# relaisarray.net
KiCad netlist of a schematic drawn in EAGLE
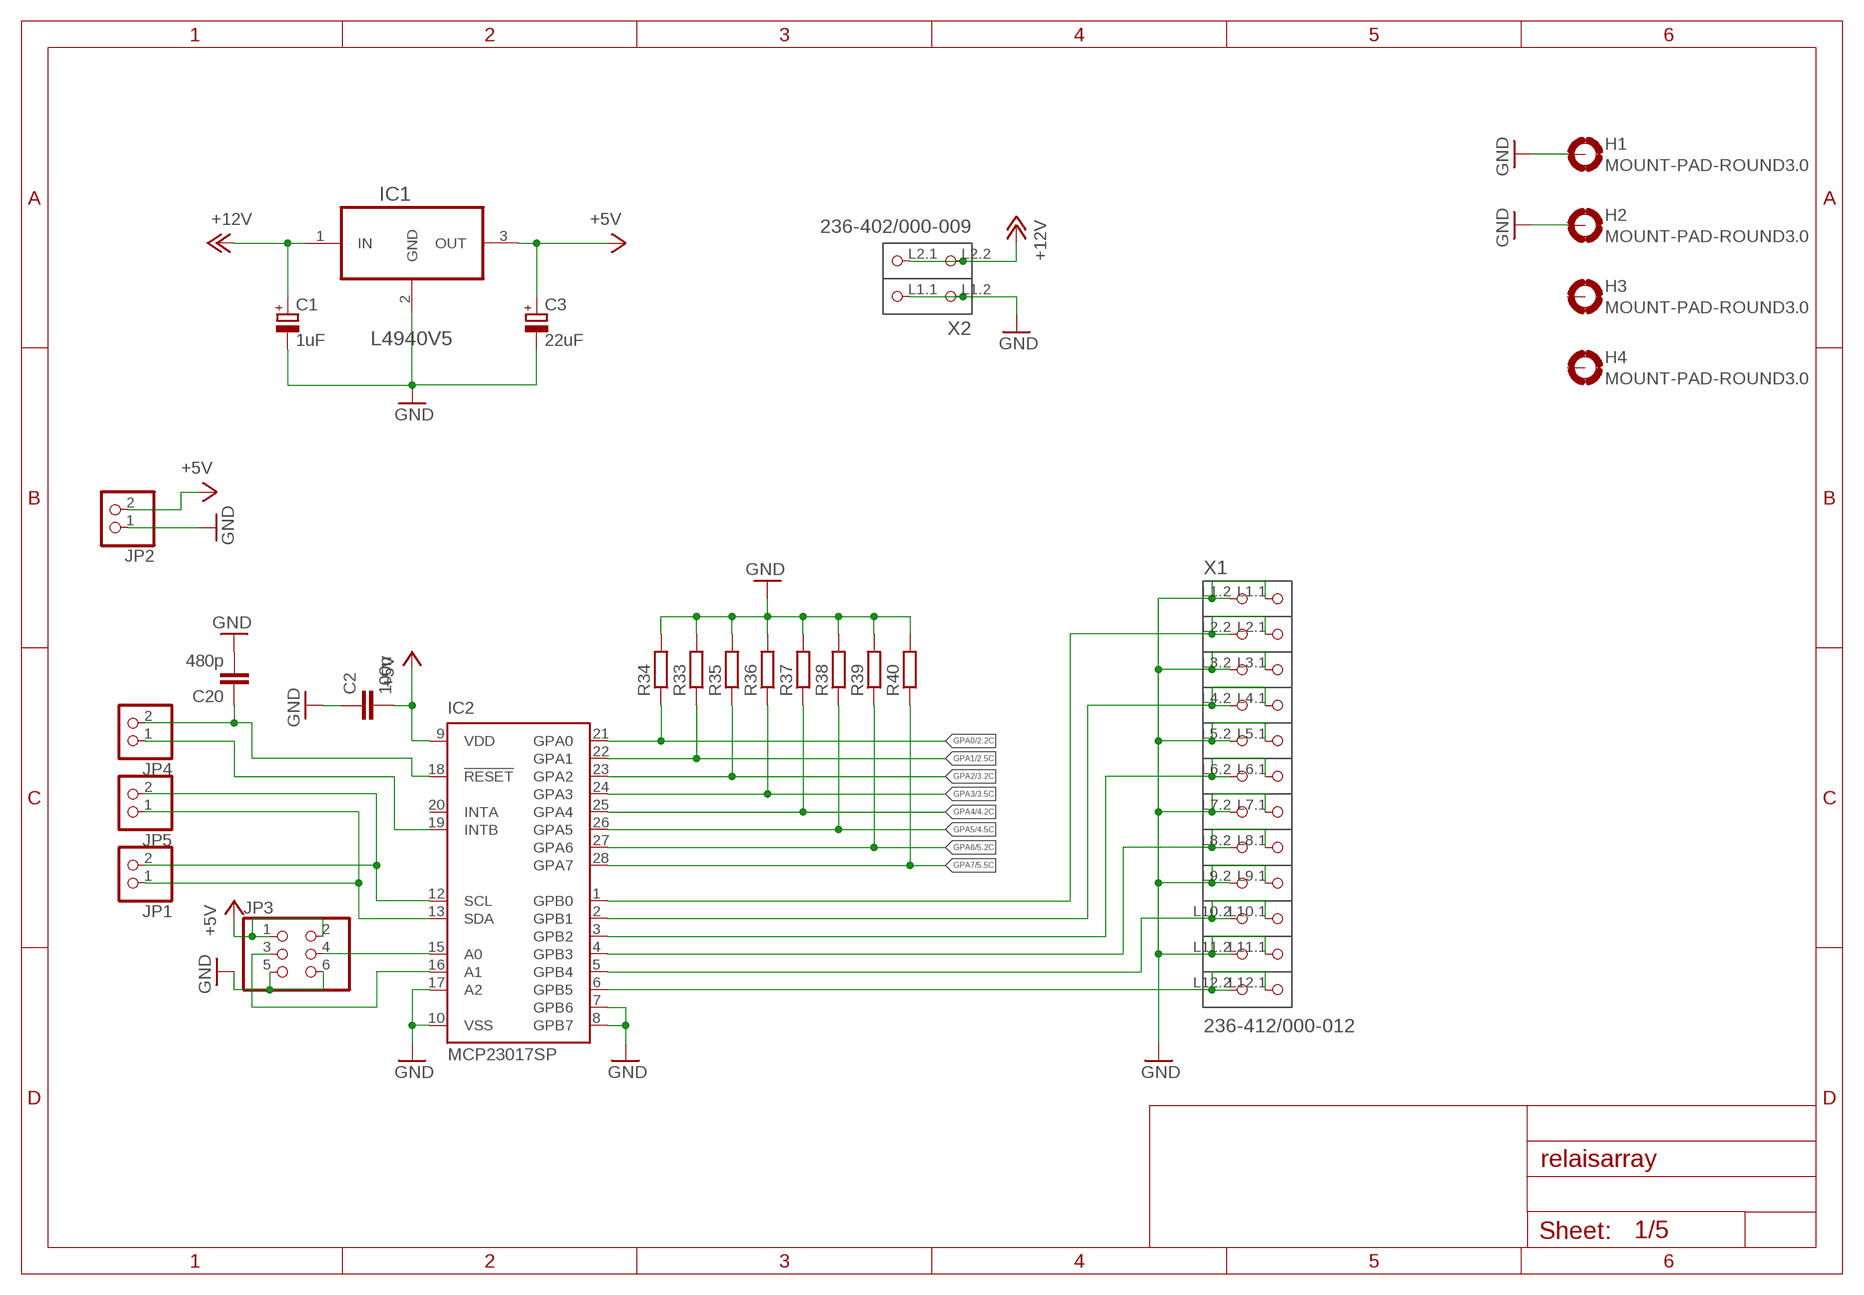
[diagram p0: schematic, sheet 1]
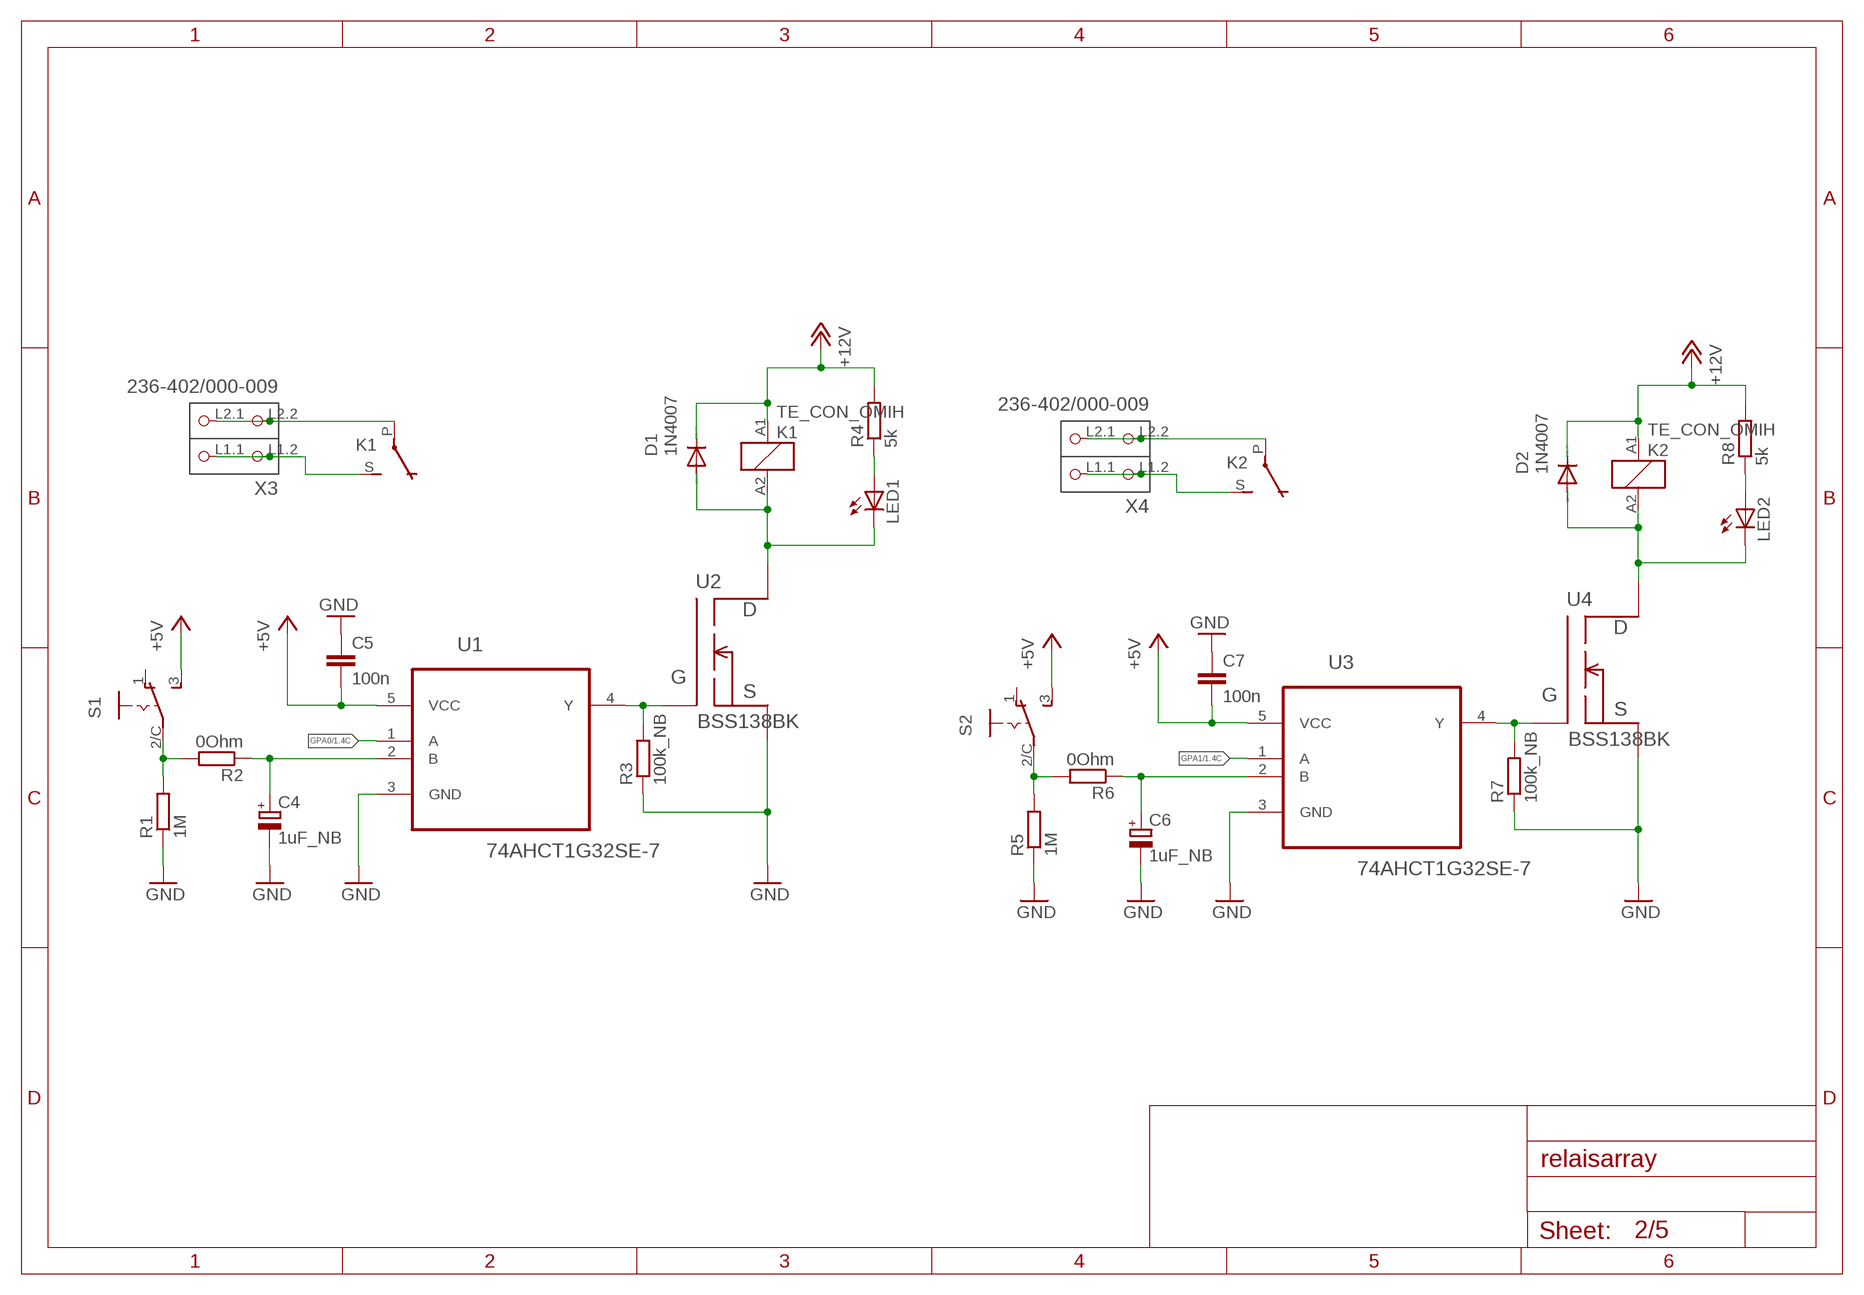
[diagram p1: schematic, sheet 2]
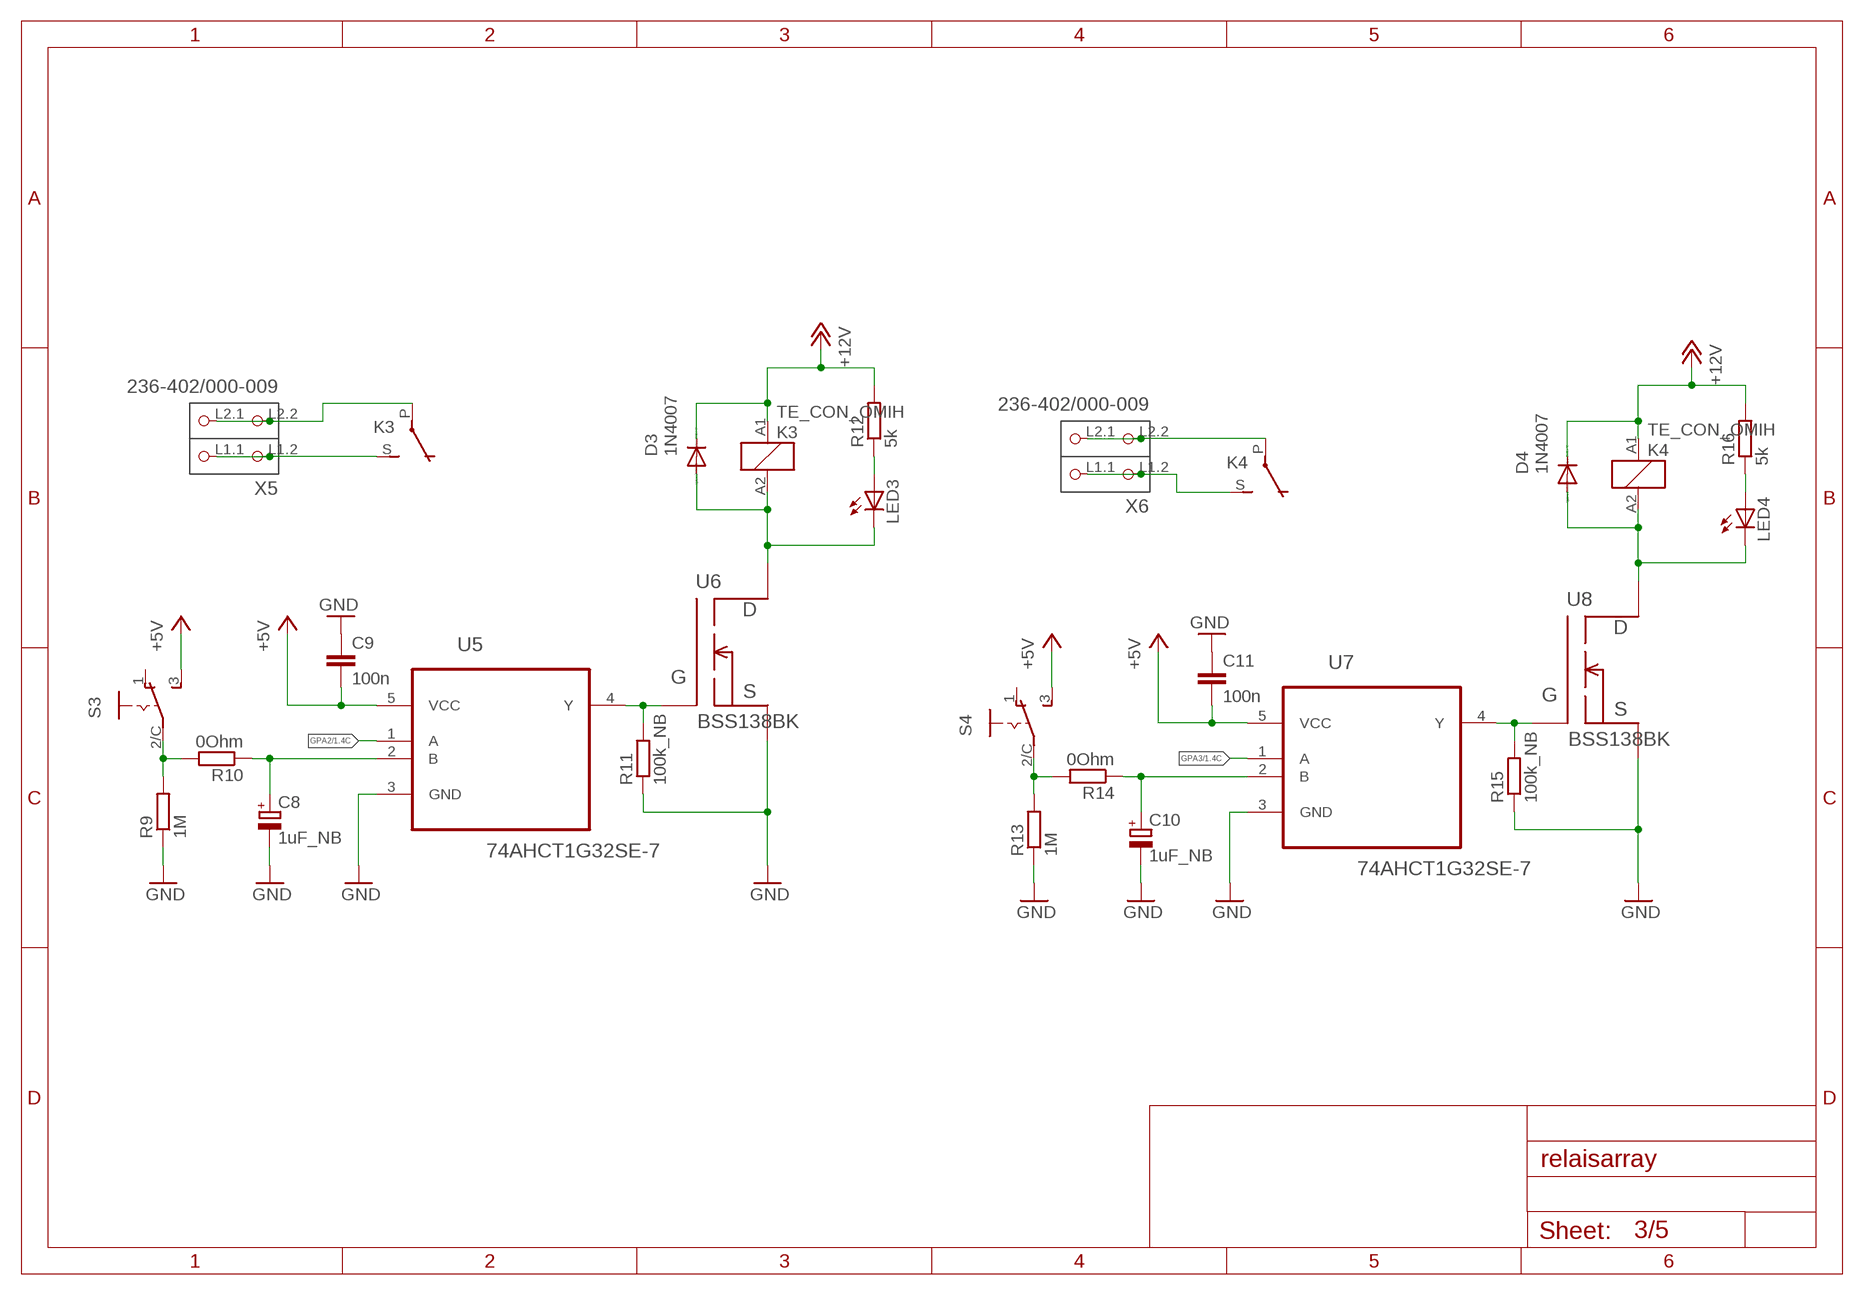
[diagram p2: schematic, sheet 3]
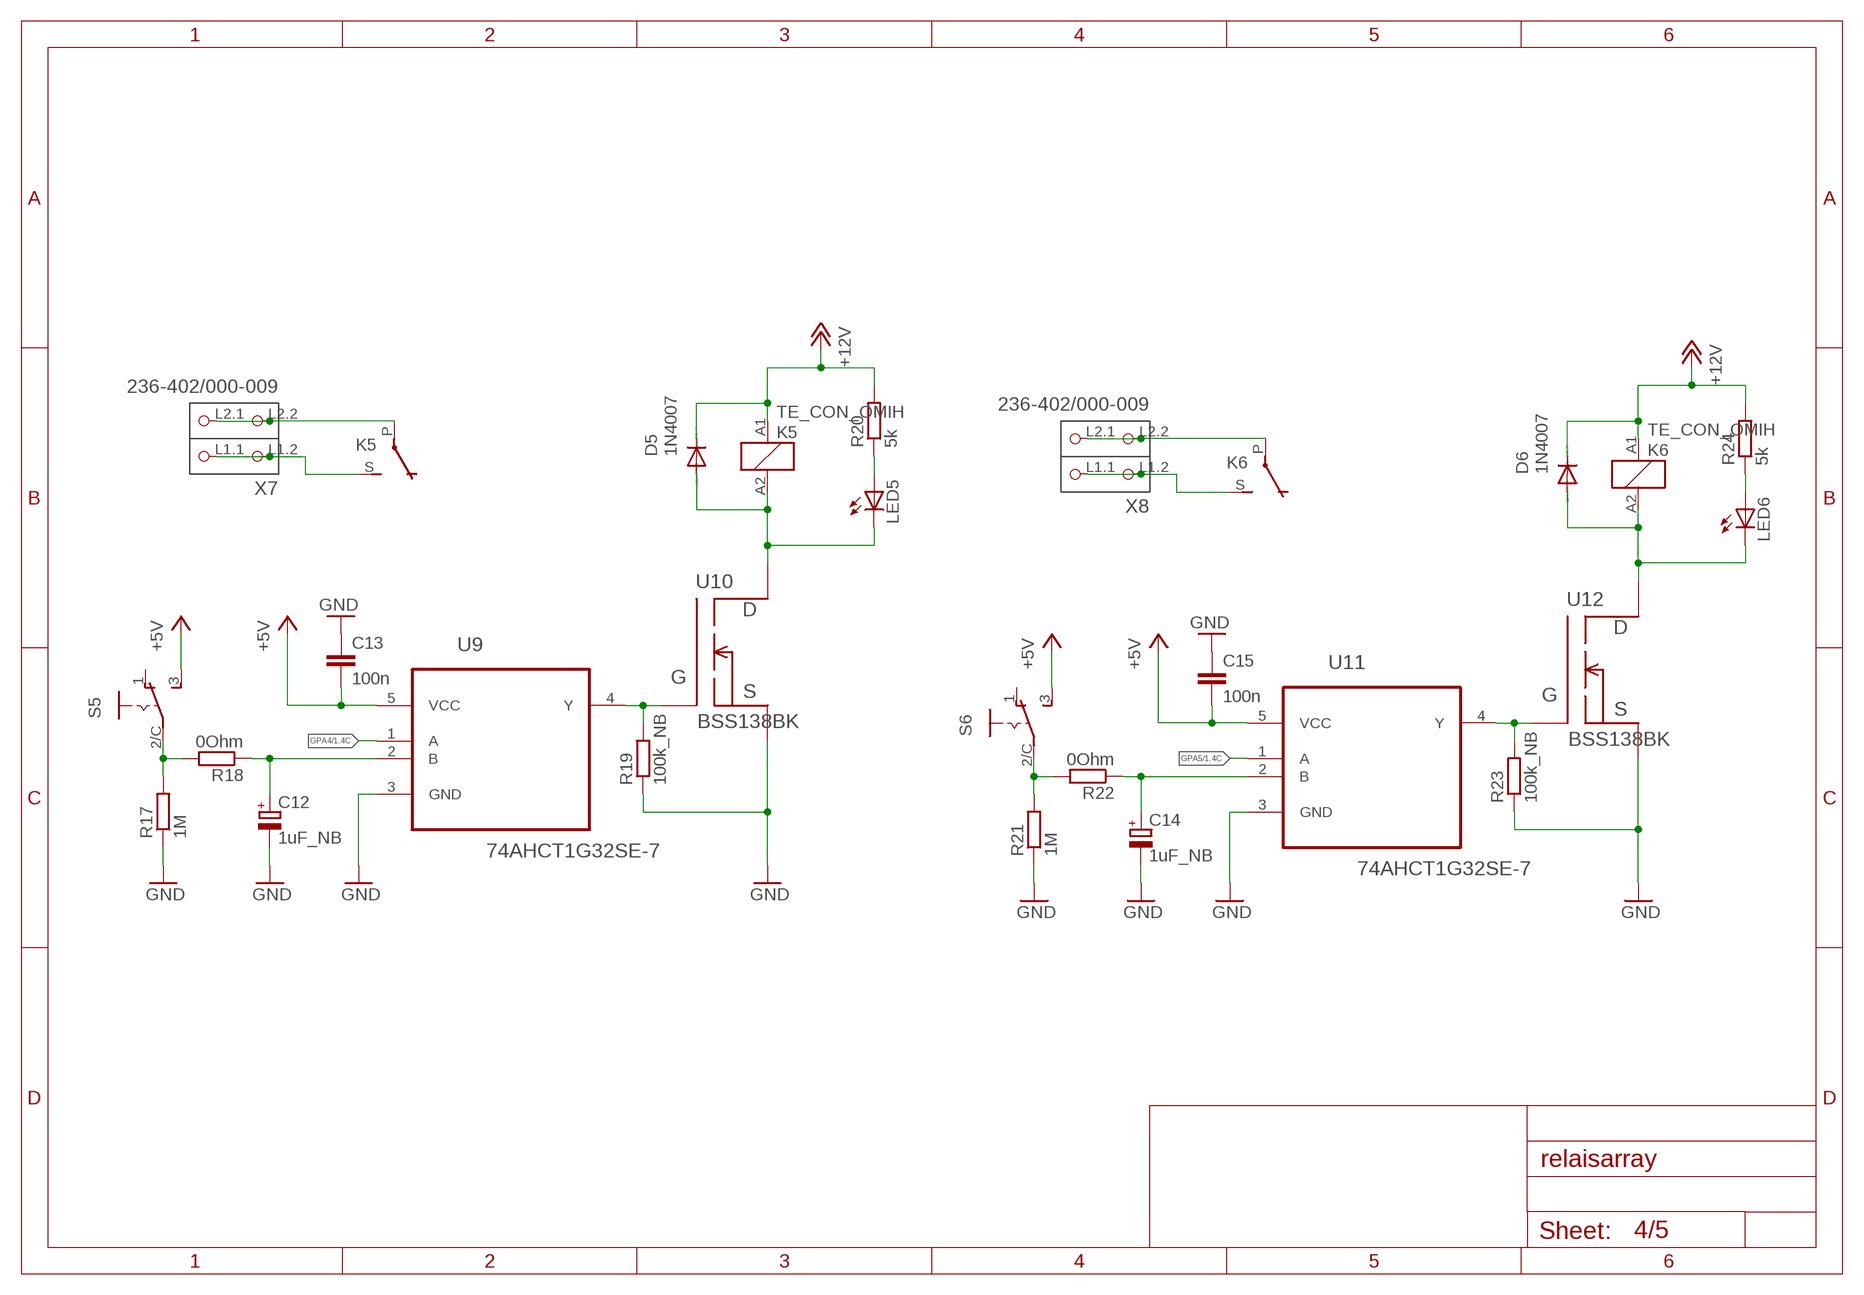
[diagram p3: schematic, sheet 4]
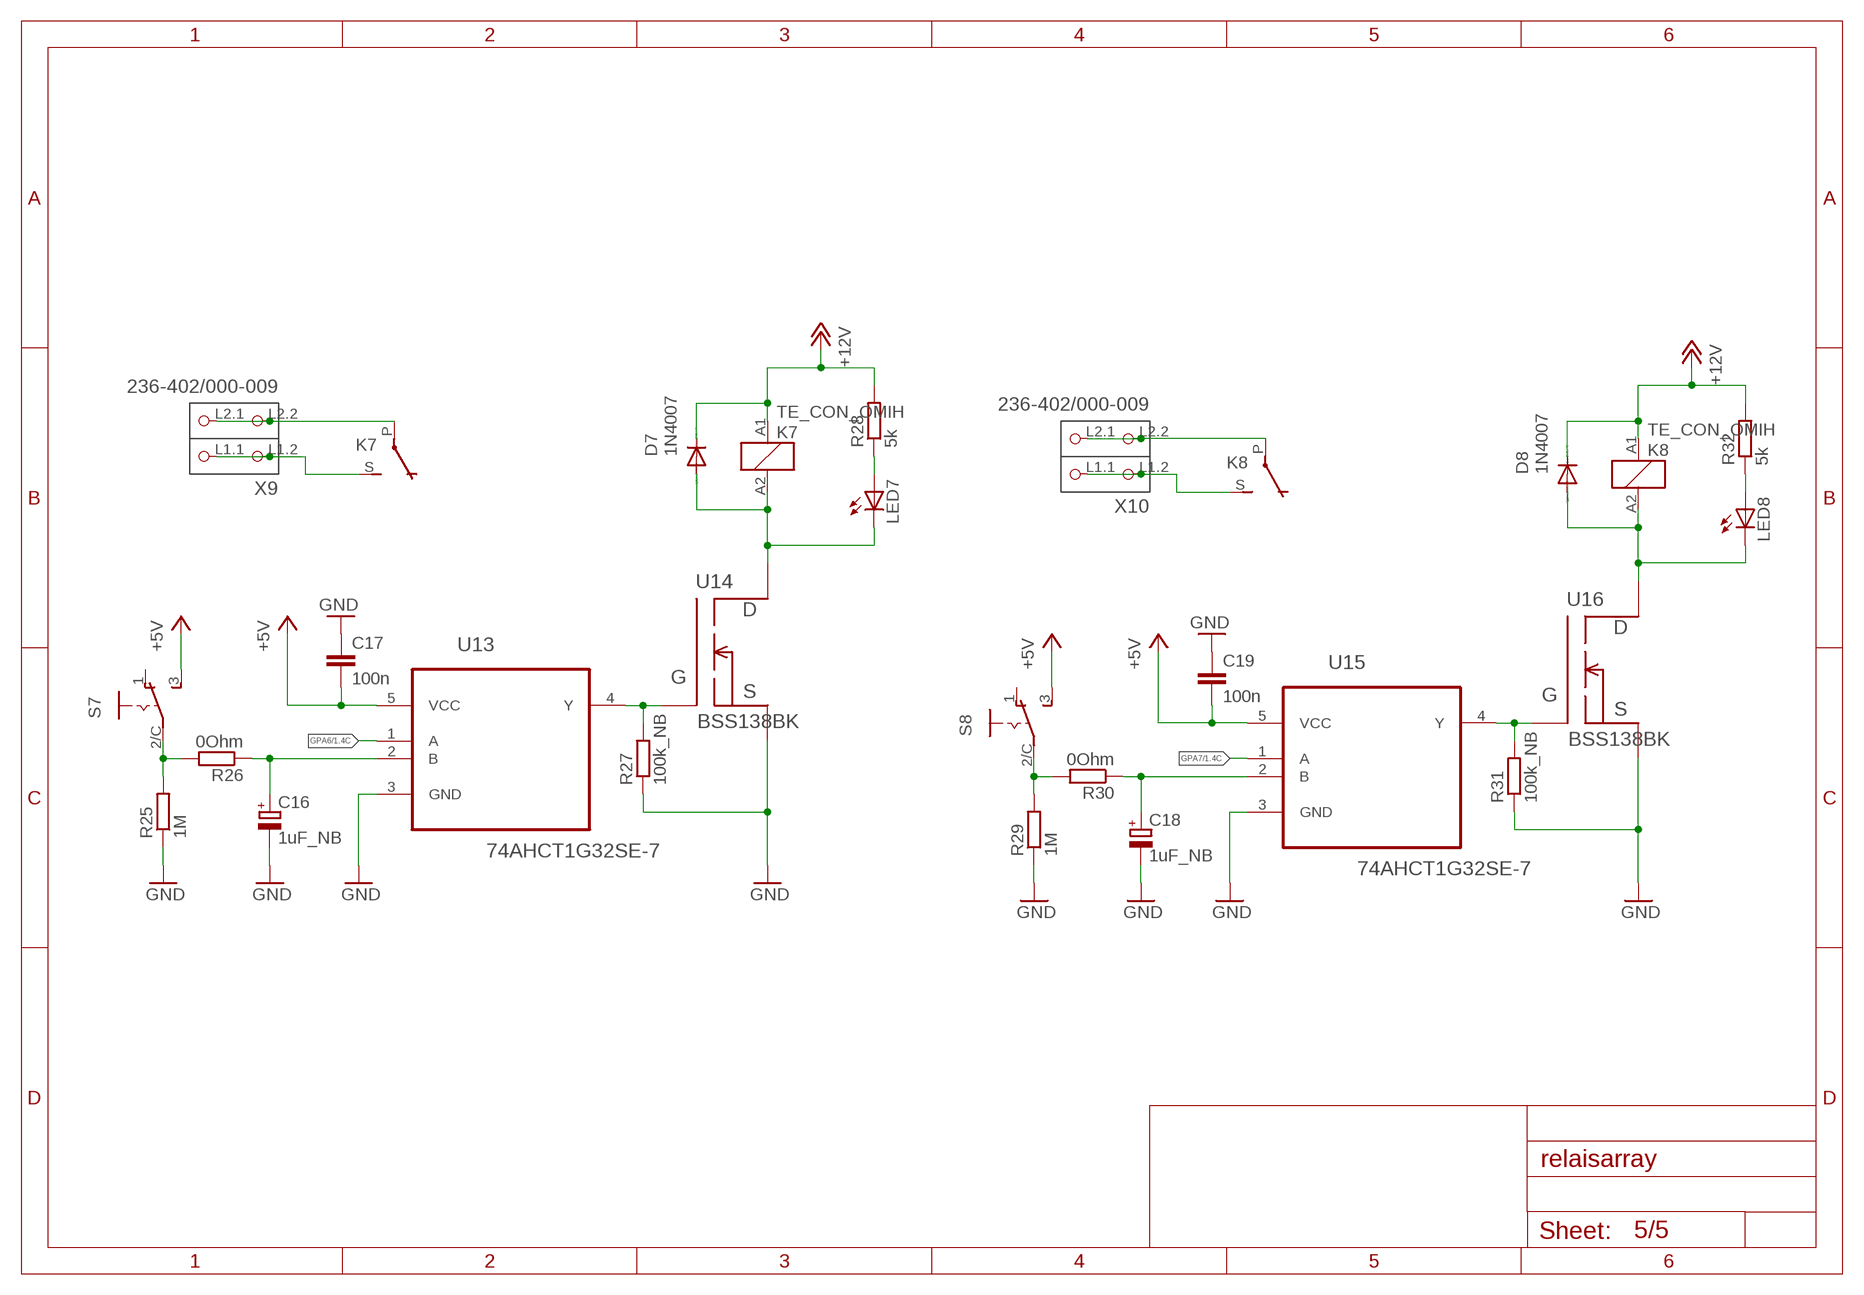
[diagram p4: schematic, sheet 5]

(export (version "E")
  (design (tool "Eeschema 10.0.6"))
  (components
    (comp (ref "C8")
      (value "1uF_NB")
      (footprint "eagle-import:TT2D5")
      (libsource (lib "eagle-import") (part "CPOL-EUTT2D5"))
    )
    (comp (ref "C9")
      (value "100n")
      (footprint "eagle-import:C050-035X075")
      (libsource (lib "eagle-import") (part "C-EU050-035X075"))
    )
    (comp (ref "C10")
      (value "1uF_NB")
      (footprint "eagle-import:TT2D5")
      (libsource (lib "eagle-import") (part "CPOL-EUTT2D5"))
    )
    (comp (ref "C11")
      (value "100n")
      (footprint "eagle-import:C050-035X075")
      (libsource (lib "eagle-import") (part "C-EU050-035X075"))
    )
    (comp (ref "D3")
      (value "1N4007")
      (footprint "eagle-import:DO41-10")
      (libsource (lib "eagle-import") (part "1N4004"))
    )
    (comp (ref "D4")
      (value "1N4007")
      (footprint "eagle-import:DO41-10")
      (libsource (lib "eagle-import") (part "1N4004"))
    )
    (comp (ref "K3")
      (value "TE_CON_OMIH")
      (footprint "eagle-import:TE_CON_OMIH")
      (libsource (lib "eagle-import") (part "TE_CON_OMIH"))
    )
    (comp (ref "K4")
      (value "TE_CON_OMIH")
      (footprint "eagle-import:TE_CON_OMIH")
      (libsource (lib "eagle-import") (part "TE_CON_OMIH"))
    )
    (comp (ref "LED3")
      (value "LED5MM")
      (footprint "eagle-import:LED5MM")
      (libsource (lib "eagle-import") (part "LED5MM"))
    )
    (comp (ref "LED4")
      (value "LED5MM")
      (footprint "eagle-import:LED5MM")
      (libsource (lib "eagle-import") (part "LED5MM"))
    )
    (comp (ref "R9")
      (value "1M")
      (footprint "eagle-import:0207_10")
      (libsource (lib "eagle-import") (part "R-EU_0207/10"))
    )
    (comp (ref "R10")
      (value "0Ohm")
      (footprint "eagle-import:0207_10")
      (libsource (lib "eagle-import") (part "R-EU_0207/10"))
    )
    (comp (ref "R11")
      (value "100k_NB")
      (footprint "eagle-import:0207_10")
      (libsource (lib "eagle-import") (part "R-EU_0207/10"))
    )
    (comp (ref "R12")
      (value "5k")
      (footprint "eagle-import:0207_10")
      (libsource (lib "eagle-import") (part "R-EU_0207/10"))
    )
    (comp (ref "R13")
      (value "1M")
      (footprint "eagle-import:0207_10")
      (libsource (lib "eagle-import") (part "R-EU_0207/10"))
    )
    (comp (ref "R14")
      (value "0Ohm")
      (footprint "eagle-import:0207_10")
      (libsource (lib "eagle-import") (part "R-EU_0207/10"))
    )
    (comp (ref "R15")
      (value "100k_NB")
      (footprint "eagle-import:0207_10")
      (libsource (lib "eagle-import") (part "R-EU_0207/10"))
    )
    (comp (ref "R16")
      (value "5k")
      (footprint "eagle-import:0207_10")
      (libsource (lib "eagle-import") (part "R-EU_0207/10"))
    )
    (comp (ref "S3")
      (value "OS102011MS2QS1")
      (footprint "eagle-import:OS102011MS2QS1")
      (libsource (lib "eagle-import") (part "OS102011MS2QS1"))
    )
    (comp (ref "S4")
      (value "OS102011MS2QS1")
      (footprint "eagle-import:OS102011MS2QS1")
      (libsource (lib "eagle-import") (part "OS102011MS2QS1"))
    )
    (comp (ref "U5")
      (value "74AHCT1G32SE-7")
      (footprint "eagle-import:SOT65P210X110-5N")
      (libsource (lib "eagle-import") (part "74AHCT1G32SE-7"))
    )
    (comp (ref "U6")
      (value "BSS138BK")
      (footprint "eagle-import:SOT65P210X110-3N")
      (libsource (lib "eagle-import") (part "BSS138BK"))
    )
    (comp (ref "U7")
      (value "74AHCT1G32SE-7")
      (footprint "eagle-import:SOT65P210X110-5N")
      (libsource (lib "eagle-import") (part "74AHCT1G32SE-7"))
    )
    (comp (ref "U8")
      (value "BSS138BK")
      (footprint "eagle-import:SOT65P210X110-3N")
      (libsource (lib "eagle-import") (part "BSS138BK"))
    )
    (comp (ref "X5")
      (value "236-402/000-009")
      (footprint "eagle-import:P-236-402")
      (libsource (lib "eagle-import") (part "236-402/000-009"))
    )
    (comp (ref "X6")
      (value "236-402/000-009")
      (footprint "eagle-import:P-236-402")
      (libsource (lib "eagle-import") (part "236-402/000-009"))
    )
    (comp (ref "C1")
      (value "1uF")
      (footprint "eagle-import:TT2D5")
      (libsource (lib "eagle-import") (part "CPOL-EUTT2D5"))
    )
    (comp (ref "C2")
      (value "100n")
      (footprint "eagle-import:C050-035X075")
      (libsource (lib "eagle-import") (part "C-EU050-035X075"))
    )
    (comp (ref "C3")
      (value "22uF")
      (footprint "eagle-import:TT2D5")
      (libsource (lib "eagle-import") (part "CPOL-EUTT2D5"))
    )
    (comp (ref "C20")
      (value "480p")
      (footprint "eagle-import:C050-035X075")
      (libsource (lib "eagle-import") (part "C-EU050-035X075"))
    )
    (comp (ref "H1")
      (value "MOUNT-PAD-ROUND3.0")
      (footprint "eagle-import:3,0-PAD")
      (libsource (lib "eagle-import") (part "MOUNT-PAD-ROUND3.0"))
    )
    (comp (ref "H2")
      (value "MOUNT-PAD-ROUND3.0")
      (footprint "eagle-import:3,0-PAD")
      (libsource (lib "eagle-import") (part "MOUNT-PAD-ROUND3.0"))
    )
    (comp (ref "H3")
      (value "MOUNT-PAD-ROUND3.0")
      (footprint "eagle-import:3,0-PAD")
      (libsource (lib "eagle-import") (part "MOUNT-PAD-ROUND3.0"))
    )
    (comp (ref "H4")
      (value "MOUNT-PAD-ROUND3.0")
      (footprint "eagle-import:3,0-PAD")
      (libsource (lib "eagle-import") (part "MOUNT-PAD-ROUND3.0"))
    )
    (comp (ref "IC1")
      (value "L4940V5")
      (footprint "eagle-import:TO254P482X1024X3124-3P")
      (libsource (lib "eagle-import") (part "L4940V5"))
    )
    (comp (ref "IC2")
      (value "MCP23017SP")
      (footprint "eagle-import:DIL28-3")
      (fields (field (name "MF") "MICROCHIP") (field (name "MPN") "MCP23017-E/SP"))
      (libsource (lib "eagle-import") (part "MCP23017SP"))
    )
    (comp (ref "JP1")
      (value "PINHD-1X2")
      (footprint "eagle-import:1X02")
      (libsource (lib "eagle-import") (part "PINHD-1X2"))
    )
    (comp (ref "JP2")
      (value "PINHD-1X2")
      (footprint "eagle-import:1X02")
      (libsource (lib "eagle-import") (part "PINHD-1X2"))
    )
    (comp (ref "JP3")
      (value "PINHD-2X3")
      (footprint "eagle-import:2X03")
      (libsource (lib "eagle-import") (part "PINHD-2X3"))
    )
    (comp (ref "JP4")
      (value "PINHD-1X2")
      (footprint "eagle-import:1X02")
      (libsource (lib "eagle-import") (part "PINHD-1X2"))
    )
    (comp (ref "JP5")
      (value "PINHD-1X2")
      (footprint "eagle-import:1X02")
      (libsource (lib "eagle-import") (part "PINHD-1X2"))
    )
    (comp (ref "R33")
      (value "R-EU_0207/10")
      (footprint "eagle-import:0207_10")
      (libsource (lib "eagle-import") (part "R-EU_0207/10"))
    )
    (comp (ref "R34")
      (value "R-EU_0207/10")
      (footprint "eagle-import:0207_10")
      (libsource (lib "eagle-import") (part "R-EU_0207/10"))
    )
    (comp (ref "R35")
      (value "R-EU_0207/10")
      (footprint "eagle-import:0207_10")
      (libsource (lib "eagle-import") (part "R-EU_0207/10"))
    )
    (comp (ref "R36")
      (value "R-EU_0207/10")
      (footprint "eagle-import:0207_10")
      (libsource (lib "eagle-import") (part "R-EU_0207/10"))
    )
    (comp (ref "R37")
      (value "R-EU_0207/10")
      (footprint "eagle-import:0207_10")
      (libsource (lib "eagle-import") (part "R-EU_0207/10"))
    )
    (comp (ref "R38")
      (value "R-EU_0207/10")
      (footprint "eagle-import:0207_10")
      (libsource (lib "eagle-import") (part "R-EU_0207/10"))
    )
    (comp (ref "R39")
      (value "R-EU_0207/10")
      (footprint "eagle-import:0207_10")
      (libsource (lib "eagle-import") (part "R-EU_0207/10"))
    )
    (comp (ref "R40")
      (value "R-EU_0207/10")
      (footprint "eagle-import:0207_10")
      (libsource (lib "eagle-import") (part "R-EU_0207/10"))
    )
    (comp (ref "X1")
      (value "236-412/000-012")
      (footprint "eagle-import:P-236-412")
      (libsource (lib "eagle-import") (part "236-412/000-012"))
    )
    (comp (ref "X2")
      (value "236-402/000-009")
      (footprint "eagle-import:P-236-402")
      (libsource (lib "eagle-import") (part "236-402/000-009"))
    )
    (comp (ref "C16")
      (value "1uF_NB")
      (footprint "eagle-import:TT2D5")
      (libsource (lib "eagle-import") (part "CPOL-EUTT2D5"))
    )
    (comp (ref "C17")
      (value "100n")
      (footprint "eagle-import:C050-035X075")
      (libsource (lib "eagle-import") (part "C-EU050-035X075"))
    )
    (comp (ref "C18")
      (value "1uF_NB")
      (footprint "eagle-import:TT2D5")
      (libsource (lib "eagle-import") (part "CPOL-EUTT2D5"))
    )
    (comp (ref "C19")
      (value "100n")
      (footprint "eagle-import:C050-035X075")
      (libsource (lib "eagle-import") (part "C-EU050-035X075"))
    )
    (comp (ref "D7")
      (value "1N4007")
      (footprint "eagle-import:DO41-10")
      (libsource (lib "eagle-import") (part "1N4004"))
    )
    (comp (ref "D8")
      (value "1N4007")
      (footprint "eagle-import:DO41-10")
      (libsource (lib "eagle-import") (part "1N4004"))
    )
    (comp (ref "K7")
      (value "TE_CON_OMIH")
      (footprint "eagle-import:TE_CON_OMIH")
      (libsource (lib "eagle-import") (part "TE_CON_OMIH"))
    )
    (comp (ref "K8")
      (value "TE_CON_OMIH")
      (footprint "eagle-import:TE_CON_OMIH")
      (libsource (lib "eagle-import") (part "TE_CON_OMIH"))
    )
    (comp (ref "LED7")
      (value "LED5MM")
      (footprint "eagle-import:LED5MM")
      (libsource (lib "eagle-import") (part "LED5MM"))
    )
    (comp (ref "LED8")
      (value "LED5MM")
      (footprint "eagle-import:LED5MM")
      (libsource (lib "eagle-import") (part "LED5MM"))
    )
    (comp (ref "R25")
      (value "1M")
      (footprint "eagle-import:0207_10")
      (libsource (lib "eagle-import") (part "R-EU_0207/10"))
    )
    (comp (ref "R26")
      (value "0Ohm")
      (footprint "eagle-import:0207_10")
      (libsource (lib "eagle-import") (part "R-EU_0207/10"))
    )
    (comp (ref "R27")
      (value "100k_NB")
      (footprint "eagle-import:0207_10")
      (libsource (lib "eagle-import") (part "R-EU_0207/10"))
    )
    (comp (ref "R28")
      (value "5k")
      (footprint "eagle-import:0207_10")
      (libsource (lib "eagle-import") (part "R-EU_0207/10"))
    )
    (comp (ref "R29")
      (value "1M")
      (footprint "eagle-import:0207_10")
      (libsource (lib "eagle-import") (part "R-EU_0207/10"))
    )
    (comp (ref "R30")
      (value "0Ohm")
      (footprint "eagle-import:0207_10")
      (libsource (lib "eagle-import") (part "R-EU_0207/10"))
    )
    (comp (ref "R31")
      (value "100k_NB")
      (footprint "eagle-import:0207_10")
      (libsource (lib "eagle-import") (part "R-EU_0207/10"))
    )
    (comp (ref "R32")
      (value "5k")
      (footprint "eagle-import:0207_10")
      (libsource (lib "eagle-import") (part "R-EU_0207/10"))
    )
    (comp (ref "S7")
      (value "OS102011MS2QS1")
      (footprint "eagle-import:OS102011MS2QS1")
      (libsource (lib "eagle-import") (part "OS102011MS2QS1"))
    )
    (comp (ref "S8")
      (value "OS102011MS2QS1")
      (footprint "eagle-import:OS102011MS2QS1")
      (libsource (lib "eagle-import") (part "OS102011MS2QS1"))
    )
    (comp (ref "U13")
      (value "74AHCT1G32SE-7")
      (footprint "eagle-import:SOT65P210X110-5N")
      (libsource (lib "eagle-import") (part "74AHCT1G32SE-7"))
    )
    (comp (ref "U14")
      (value "BSS138BK")
      (footprint "eagle-import:SOT65P210X110-3N")
      (libsource (lib "eagle-import") (part "BSS138BK"))
    )
    (comp (ref "U15")
      (value "74AHCT1G32SE-7")
      (footprint "eagle-import:SOT65P210X110-5N")
      (libsource (lib "eagle-import") (part "74AHCT1G32SE-7"))
    )
    (comp (ref "U16")
      (value "BSS138BK")
      (footprint "eagle-import:SOT65P210X110-3N")
      (libsource (lib "eagle-import") (part "BSS138BK"))
    )
    (comp (ref "X9")
      (value "236-402/000-009")
      (footprint "eagle-import:P-236-402")
      (libsource (lib "eagle-import") (part "236-402/000-009"))
    )
    (comp (ref "X10")
      (value "236-402/000-009")
      (footprint "eagle-import:P-236-402")
      (libsource (lib "eagle-import") (part "236-402/000-009"))
    )
    (comp (ref "C4")
      (value "1uF_NB")
      (footprint "eagle-import:TT2D5")
      (libsource (lib "eagle-import") (part "CPOL-EUTT2D5"))
    )
    (comp (ref "C5")
      (value "100n")
      (footprint "eagle-import:C050-035X075")
      (libsource (lib "eagle-import") (part "C-EU050-035X075"))
    )
    (comp (ref "C6")
      (value "1uF_NB")
      (footprint "eagle-import:TT2D5")
      (libsource (lib "eagle-import") (part "CPOL-EUTT2D5"))
    )
    (comp (ref "C7")
      (value "100n")
      (footprint "eagle-import:C050-035X075")
      (libsource (lib "eagle-import") (part "C-EU050-035X075"))
    )
    (comp (ref "D1")
      (value "1N4007")
      (footprint "eagle-import:DO41-10")
      (libsource (lib "eagle-import") (part "1N4004"))
    )
    (comp (ref "D2")
      (value "1N4007")
      (footprint "eagle-import:DO41-10")
      (libsource (lib "eagle-import") (part "1N4004"))
    )
    (comp (ref "K1")
      (value "TE_CON_OMIH")
      (footprint "eagle-import:TE_CON_OMIH")
      (libsource (lib "eagle-import") (part "TE_CON_OMIH"))
    )
    (comp (ref "K2")
      (value "TE_CON_OMIH")
      (footprint "eagle-import:TE_CON_OMIH")
      (libsource (lib "eagle-import") (part "TE_CON_OMIH"))
    )
    (comp (ref "LED1")
      (value "LED5MM")
      (footprint "eagle-import:LED5MM")
      (libsource (lib "eagle-import") (part "LED5MM"))
    )
    (comp (ref "LED2")
      (value "LED5MM")
      (footprint "eagle-import:LED5MM")
      (libsource (lib "eagle-import") (part "LED5MM"))
    )
    (comp (ref "R1")
      (value "1M")
      (footprint "eagle-import:0207_10")
      (libsource (lib "eagle-import") (part "R-EU_0207/10"))
    )
    (comp (ref "R2")
      (value "0Ohm")
      (footprint "eagle-import:0207_10")
      (libsource (lib "eagle-import") (part "R-EU_0207/10"))
    )
    (comp (ref "R3")
      (value "100k_NB")
      (footprint "eagle-import:0207_10")
      (libsource (lib "eagle-import") (part "R-EU_0207/10"))
    )
    (comp (ref "R4")
      (value "5k")
      (footprint "eagle-import:0207_10")
      (libsource (lib "eagle-import") (part "R-EU_0207/10"))
    )
    (comp (ref "R5")
      (value "1M")
      (footprint "eagle-import:0207_10")
      (libsource (lib "eagle-import") (part "R-EU_0207/10"))
    )
    (comp (ref "R6")
      (value "0Ohm")
      (footprint "eagle-import:0207_10")
      (libsource (lib "eagle-import") (part "R-EU_0207/10"))
    )
    (comp (ref "R7")
      (value "100k_NB")
      (footprint "eagle-import:0207_10")
      (libsource (lib "eagle-import") (part "R-EU_0207/10"))
    )
    (comp (ref "R8")
      (value "5k")
      (footprint "eagle-import:0207_10")
      (libsource (lib "eagle-import") (part "R-EU_0207/10"))
    )
    (comp (ref "S1")
      (value "OS102011MS2QS1")
      (footprint "eagle-import:OS102011MS2QS1")
      (libsource (lib "eagle-import") (part "OS102011MS2QS1"))
    )
    (comp (ref "S2")
      (value "OS102011MS2QS1")
      (footprint "eagle-import:OS102011MS2QS1")
      (libsource (lib "eagle-import") (part "OS102011MS2QS1"))
    )
    (comp (ref "U1")
      (value "74AHCT1G32SE-7")
      (footprint "eagle-import:SOT65P210X110-5N")
      (libsource (lib "eagle-import") (part "74AHCT1G32SE-7"))
    )
    (comp (ref "U2")
      (value "BSS138BK")
      (footprint "eagle-import:SOT65P210X110-3N")
      (libsource (lib "eagle-import") (part "BSS138BK"))
    )
    (comp (ref "U3")
      (value "74AHCT1G32SE-7")
      (footprint "eagle-import:SOT65P210X110-5N")
      (libsource (lib "eagle-import") (part "74AHCT1G32SE-7"))
    )
    (comp (ref "U4")
      (value "BSS138BK")
      (footprint "eagle-import:SOT65P210X110-3N")
      (libsource (lib "eagle-import") (part "BSS138BK"))
    )
    (comp (ref "X3")
      (value "236-402/000-009")
      (footprint "eagle-import:P-236-402")
      (libsource (lib "eagle-import") (part "236-402/000-009"))
    )
    (comp (ref "X4")
      (value "236-402/000-009")
      (footprint "eagle-import:P-236-402")
      (libsource (lib "eagle-import") (part "236-402/000-009"))
    )
    (comp (ref "C12")
      (value "1uF_NB")
      (footprint "eagle-import:TT2D5")
      (libsource (lib "eagle-import") (part "CPOL-EUTT2D5"))
    )
    (comp (ref "C13")
      (value "100n")
      (footprint "eagle-import:C050-035X075")
      (libsource (lib "eagle-import") (part "C-EU050-035X075"))
    )
    (comp (ref "C14")
      (value "1uF_NB")
      (footprint "eagle-import:TT2D5")
      (libsource (lib "eagle-import") (part "CPOL-EUTT2D5"))
    )
    (comp (ref "C15")
      (value "100n")
      (footprint "eagle-import:C050-035X075")
      (libsource (lib "eagle-import") (part "C-EU050-035X075"))
    )
    (comp (ref "D5")
      (value "1N4007")
      (footprint "eagle-import:DO41-10")
      (libsource (lib "eagle-import") (part "1N4004"))
    )
    (comp (ref "D6")
      (value "1N4007")
      (footprint "eagle-import:DO41-10")
      (libsource (lib "eagle-import") (part "1N4004"))
    )
    (comp (ref "K5")
      (value "TE_CON_OMIH")
      (footprint "eagle-import:TE_CON_OMIH")
      (libsource (lib "eagle-import") (part "TE_CON_OMIH"))
    )
    (comp (ref "K6")
      (value "TE_CON_OMIH")
      (footprint "eagle-import:TE_CON_OMIH")
      (libsource (lib "eagle-import") (part "TE_CON_OMIH"))
    )
    (comp (ref "LED5")
      (value "LED5MM")
      (footprint "eagle-import:LED5MM")
      (libsource (lib "eagle-import") (part "LED5MM"))
    )
    (comp (ref "LED6")
      (value "LED5MM")
      (footprint "eagle-import:LED5MM")
      (libsource (lib "eagle-import") (part "LED5MM"))
    )
    (comp (ref "R17")
      (value "1M")
      (footprint "eagle-import:0207_10")
      (libsource (lib "eagle-import") (part "R-EU_0207/10"))
    )
    (comp (ref "R18")
      (value "0Ohm")
      (footprint "eagle-import:0207_10")
      (libsource (lib "eagle-import") (part "R-EU_0207/10"))
    )
    (comp (ref "R19")
      (value "100k_NB")
      (footprint "eagle-import:0207_10")
      (libsource (lib "eagle-import") (part "R-EU_0207/10"))
    )
    (comp (ref "R20")
      (value "5k")
      (footprint "eagle-import:0207_10")
      (libsource (lib "eagle-import") (part "R-EU_0207/10"))
    )
    (comp (ref "R21")
      (value "1M")
      (footprint "eagle-import:0207_10")
      (libsource (lib "eagle-import") (part "R-EU_0207/10"))
    )
    (comp (ref "R22")
      (value "0Ohm")
      (footprint "eagle-import:0207_10")
      (libsource (lib "eagle-import") (part "R-EU_0207/10"))
    )
    (comp (ref "R23")
      (value "100k_NB")
      (footprint "eagle-import:0207_10")
      (libsource (lib "eagle-import") (part "R-EU_0207/10"))
    )
    (comp (ref "R24")
      (value "5k")
      (footprint "eagle-import:0207_10")
      (libsource (lib "eagle-import") (part "R-EU_0207/10"))
    )
    (comp (ref "S5")
      (value "OS102011MS2QS1")
      (footprint "eagle-import:OS102011MS2QS1")
      (libsource (lib "eagle-import") (part "OS102011MS2QS1"))
    )
    (comp (ref "S6")
      (value "OS102011MS2QS1")
      (footprint "eagle-import:OS102011MS2QS1")
      (libsource (lib "eagle-import") (part "OS102011MS2QS1"))
    )
    (comp (ref "U9")
      (value "74AHCT1G32SE-7")
      (footprint "eagle-import:SOT65P210X110-5N")
      (libsource (lib "eagle-import") (part "74AHCT1G32SE-7"))
    )
    (comp (ref "U10")
      (value "BSS138BK")
      (footprint "eagle-import:SOT65P210X110-3N")
      (libsource (lib "eagle-import") (part "BSS138BK"))
    )
    (comp (ref "U11")
      (value "74AHCT1G32SE-7")
      (footprint "eagle-import:SOT65P210X110-5N")
      (libsource (lib "eagle-import") (part "74AHCT1G32SE-7"))
    )
    (comp (ref "U12")
      (value "BSS138BK")
      (footprint "eagle-import:SOT65P210X110-3N")
      (libsource (lib "eagle-import") (part "BSS138BK"))
    )
    (comp (ref "X7")
      (value "236-402/000-009")
      (footprint "eagle-import:P-236-402")
      (libsource (lib "eagle-import") (part "236-402/000-009"))
    )
    (comp (ref "X8")
      (value "236-402/000-009")
      (footprint "eagle-import:P-236-402")
      (libsource (lib "eagle-import") (part "236-402/000-009"))
    )
  )
  (nets
    (net (code "1") (name "+5V") (class "Default")
      (node (ref "C11") (pin "2") (pinfunction "2_2") (pintype "passive"))
      (node (ref "C13") (pin "2") (pinfunction "2_2") (pintype "passive"))
      (node (ref "C15") (pin "2") (pinfunction "2_2") (pintype "passive"))
      (node (ref "C17") (pin "2") (pinfunction "2_2") (pintype "passive"))
      (node (ref "C19") (pin "2") (pinfunction "2_2") (pintype "passive"))
      (node (ref "C2") (pin "2") (pinfunction "2_2") (pintype "passive"))
      (node (ref "C3") (pin "+") (pinfunction "+_+") (pintype "passive"))
      (node (ref "C5") (pin "2") (pinfunction "2_2") (pintype "passive"))
      (node (ref "C7") (pin "2") (pinfunction "2_2") (pintype "passive"))
      (node (ref "C9") (pin "2") (pinfunction "2_2") (pintype "passive"))
      (node (ref "IC1") (pin "3") (pinfunction "OUT_3") (pintype "output"))
      (node (ref "IC2") (pin "9") (pinfunction "VDD_9") (pintype "power_in"))
      (node (ref "JP2") (pin "2") (pinfunction "2_2") (pintype "passive"))
      (node (ref "JP3") (pin "1") (pinfunction "1_1") (pintype "passive"))
      (node (ref "JP3") (pin "2") (pinfunction "2_2") (pintype "passive"))
      (node (ref "S1") (pin "3") (pinfunction "3_3") (pintype "passive"))
      (node (ref "S2") (pin "3") (pinfunction "3_3") (pintype "passive"))
      (node (ref "S3") (pin "3") (pinfunction "3_3") (pintype "passive"))
      (node (ref "S4") (pin "3") (pinfunction "3_3") (pintype "passive"))
      (node (ref "S5") (pin "3") (pinfunction "3_3") (pintype "passive"))
      (node (ref "S6") (pin "3") (pinfunction "3_3") (pintype "passive"))
      (node (ref "S7") (pin "3") (pinfunction "3_3") (pintype "passive"))
      (node (ref "S8") (pin "3") (pinfunction "3_3") (pintype "passive"))
      (node (ref "U1") (pin "5") (pinfunction "VCC_5") (pintype "power_in"))
      (node (ref "U11") (pin "5") (pinfunction "VCC_5") (pintype "power_in"))
      (node (ref "U13") (pin "5") (pinfunction "VCC_5") (pintype "power_in"))
      (node (ref "U15") (pin "5") (pinfunction "VCC_5") (pintype "power_in"))
      (node (ref "U3") (pin "5") (pinfunction "VCC_5") (pintype "power_in"))
      (node (ref "U5") (pin "5") (pinfunction "VCC_5") (pintype "power_in"))
      (node (ref "U7") (pin "5") (pinfunction "VCC_5") (pintype "power_in"))
      (node (ref "U9") (pin "5") (pinfunction "VCC_5") (pintype "power_in"))
    )
    (net (code "2") (name "+12V") (class "Default")
      (node (ref "C1") (pin "+") (pinfunction "+_+") (pintype "passive"))
      (node (ref "D1") (pin "C") (pinfunction "C_C") (pintype "passive"))
      (node (ref "D2") (pin "C") (pinfunction "C_C") (pintype "passive"))
      (node (ref "D3") (pin "C") (pinfunction "C_C") (pintype "passive"))
      (node (ref "D4") (pin "C") (pinfunction "C_C") (pintype "passive"))
      (node (ref "D5") (pin "C") (pinfunction "C_C") (pintype "passive"))
      (node (ref "D6") (pin "C") (pinfunction "C_C") (pintype "passive"))
      (node (ref "D7") (pin "C") (pinfunction "C_C") (pintype "passive"))
      (node (ref "D8") (pin "C") (pinfunction "C_C") (pintype "passive"))
      (node (ref "IC1") (pin "1") (pinfunction "IN_1") (pintype "input"))
      (node (ref "K1") (pin "A1") (pinfunction "A1_A1") (pintype "passive"))
      (node (ref "K2") (pin "A1") (pinfunction "A1_A1") (pintype "passive"))
      (node (ref "K3") (pin "A1") (pinfunction "A1_A1") (pintype "passive"))
      (node (ref "K4") (pin "A1") (pinfunction "A1_A1") (pintype "passive"))
      (node (ref "K5") (pin "A1") (pinfunction "A1_A1") (pintype "passive"))
      (node (ref "K6") (pin "A1") (pinfunction "A1_A1") (pintype "passive"))
      (node (ref "K7") (pin "A1") (pinfunction "A1_A1") (pintype "passive"))
      (node (ref "K8") (pin "A1") (pinfunction "A1_A1") (pintype "passive"))
      (node (ref "R12") (pin "2") (pinfunction "2_2") (pintype "passive"))
      (node (ref "R16") (pin "2") (pinfunction "2_2") (pintype "passive"))
      (node (ref "R20") (pin "2") (pinfunction "2_2") (pintype "passive"))
      (node (ref "R24") (pin "2") (pinfunction "2_2") (pintype "passive"))
      (node (ref "R28") (pin "2") (pinfunction "2_2") (pintype "passive"))
      (node (ref "R32") (pin "2") (pinfunction "2_2") (pintype "passive"))
      (node (ref "R4") (pin "2") (pinfunction "2_2") (pintype "passive"))
      (node (ref "R8") (pin "2") (pinfunction "2_2") (pintype "passive"))
      (node (ref "X2") (pin "L2.1") (pinfunction "P2.1_L2.1") (pintype "bidirectional"))
      (node (ref "X2") (pin "L2.2") (pinfunction "P2.2_L2.2") (pintype "bidirectional"))
    )
    (net (code "3") (name "GND") (class "Default")
      (node (ref "C1") (pin "-") (pinfunction "-_-") (pintype "passive"))
      (node (ref "C10") (pin "-") (pinfunction "-_-") (pintype "passive"))
      (node (ref "C11") (pin "1") (pinfunction "1_1") (pintype "passive"))
      (node (ref "C12") (pin "-") (pinfunction "-_-") (pintype "passive"))
      (node (ref "C13") (pin "1") (pinfunction "1_1") (pintype "passive"))
      (node (ref "C14") (pin "-") (pinfunction "-_-") (pintype "passive"))
      (node (ref "C15") (pin "1") (pinfunction "1_1") (pintype "passive"))
      (node (ref "C16") (pin "-") (pinfunction "-_-") (pintype "passive"))
      (node (ref "C17") (pin "1") (pinfunction "1_1") (pintype "passive"))
      (node (ref "C18") (pin "-") (pinfunction "-_-") (pintype "passive"))
      (node (ref "C19") (pin "1") (pinfunction "1_1") (pintype "passive"))
      (node (ref "C2") (pin "1") (pinfunction "1_1") (pintype "passive"))
      (node (ref "C20") (pin "2") (pinfunction "2_2") (pintype "passive"))
      (node (ref "C3") (pin "-") (pinfunction "-_-") (pintype "passive"))
      (node (ref "C4") (pin "-") (pinfunction "-_-") (pintype "passive"))
      (node (ref "C5") (pin "1") (pinfunction "1_1") (pintype "passive"))
      (node (ref "C6") (pin "-") (pinfunction "-_-") (pintype "passive"))
      (node (ref "C7") (pin "1") (pinfunction "1_1") (pintype "passive"))
      (node (ref "C8") (pin "-") (pinfunction "-_-") (pintype "passive"))
      (node (ref "C9") (pin "1") (pinfunction "1_1") (pintype "passive"))
      (node (ref "H1") (pin "B3,0") (pinfunction "MOUNT_B3,0") (pintype "passive"))
      (node (ref "H2") (pin "B3,0") (pinfunction "MOUNT_B3,0") (pintype "passive"))
      (node (ref "IC1") (pin "2") (pinfunction "GND_2") (pintype "passive"))
      (node (ref "IC2") (pin "10") (pinfunction "VSS_10") (pintype "power_in"))
      (node (ref "IC2") (pin "17") (pinfunction "A2_17") (pintype "input"))
      (node (ref "IC2") (pin "7") (pinfunction "GPB6_7") (pintype "bidirectional"))
      (node (ref "IC2") (pin "8") (pinfunction "GPB7_8") (pintype "bidirectional"))
      (node (ref "JP2") (pin "1") (pinfunction "1_1") (pintype "passive"))
      (node (ref "JP3") (pin "5") (pinfunction "5_5") (pintype "passive"))
      (node (ref "JP3") (pin "6") (pinfunction "6_6") (pintype "passive"))
      (node (ref "R1") (pin "1") (pinfunction "1_1") (pintype "passive"))
      (node (ref "R11") (pin "1") (pinfunction "1_1") (pintype "passive"))
      (node (ref "R13") (pin "1") (pinfunction "1_1") (pintype "passive"))
      (node (ref "R15") (pin "1") (pinfunction "1_1") (pintype "passive"))
      (node (ref "R17") (pin "1") (pinfunction "1_1") (pintype "passive"))
      (node (ref "R19") (pin "1") (pinfunction "1_1") (pintype "passive"))
      (node (ref "R21") (pin "1") (pinfunction "1_1") (pintype "passive"))
      (node (ref "R23") (pin "1") (pinfunction "1_1") (pintype "passive"))
      (node (ref "R25") (pin "1") (pinfunction "1_1") (pintype "passive"))
      (node (ref "R27") (pin "1") (pinfunction "1_1") (pintype "passive"))
      (node (ref "R29") (pin "1") (pinfunction "1_1") (pintype "passive"))
      (node (ref "R3") (pin "1") (pinfunction "1_1") (pintype "passive"))
      (node (ref "R31") (pin "1") (pinfunction "1_1") (pintype "passive"))
      (node (ref "R33") (pin "2") (pinfunction "2_2") (pintype "passive"))
      (node (ref "R34") (pin "2") (pinfunction "2_2") (pintype "passive"))
      (node (ref "R35") (pin "2") (pinfunction "2_2") (pintype "passive"))
      (node (ref "R36") (pin "2") (pinfunction "2_2") (pintype "passive"))
      (node (ref "R37") (pin "2") (pinfunction "2_2") (pintype "passive"))
      (node (ref "R38") (pin "2") (pinfunction "2_2") (pintype "passive"))
      (node (ref "R39") (pin "2") (pinfunction "2_2") (pintype "passive"))
      (node (ref "R40") (pin "2") (pinfunction "2_2") (pintype "passive"))
      (node (ref "R5") (pin "1") (pinfunction "1_1") (pintype "passive"))
      (node (ref "R7") (pin "1") (pinfunction "1_1") (pintype "passive"))
      (node (ref "R9") (pin "1") (pinfunction "1_1") (pintype "passive"))
      (node (ref "U1") (pin "3") (pinfunction "GND_3") (pintype "passive"))
      (node (ref "U10") (pin "2") (pinfunction "S_2") (pintype "passive"))
      (node (ref "U11") (pin "3") (pinfunction "GND_3") (pintype "passive"))
      (node (ref "U12") (pin "2") (pinfunction "S_2") (pintype "passive"))
      (node (ref "U13") (pin "3") (pinfunction "GND_3") (pintype "passive"))
      (node (ref "U14") (pin "2") (pinfunction "S_2") (pintype "passive"))
      (node (ref "U15") (pin "3") (pinfunction "GND_3") (pintype "passive"))
      (node (ref "U16") (pin "2") (pinfunction "S_2") (pintype "passive"))
      (node (ref "U2") (pin "2") (pinfunction "S_2") (pintype "passive"))
      (node (ref "U3") (pin "3") (pinfunction "GND_3") (pintype "passive"))
      (node (ref "U4") (pin "2") (pinfunction "S_2") (pintype "passive"))
      (node (ref "U5") (pin "3") (pinfunction "GND_3") (pintype "passive"))
      (node (ref "U6") (pin "2") (pinfunction "S_2") (pintype "passive"))
      (node (ref "U7") (pin "3") (pinfunction "GND_3") (pintype "passive"))
      (node (ref "U8") (pin "2") (pinfunction "S_2") (pintype "passive"))
      (node (ref "U9") (pin "3") (pinfunction "GND_3") (pintype "passive"))
      (node (ref "X1") (pin "L1.1") (pinfunction "P1.1_L1.1") (pintype "bidirectional"))
      (node (ref "X1") (pin "L1.2") (pinfunction "P1.2_L1.2") (pintype "bidirectional"))
      (node (ref "X1") (pin "L11.1") (pinfunction "P11.1_L11.1") (pintype "bidirectional"))
      (node (ref "X1") (pin "L11.2") (pinfunction "P11.2_L11.2") (pintype "bidirectional"))
      (node (ref "X1") (pin "L3.1") (pinfunction "P3.1_L3.1") (pintype "bidirectional"))
      (node (ref "X1") (pin "L3.2") (pinfunction "P3.2_L3.2") (pintype "bidirectional"))
      (node (ref "X1") (pin "L5.1") (pinfunction "P5.1_L5.1") (pintype "bidirectional"))
      (node (ref "X1") (pin "L5.2") (pinfunction "P5.2_L5.2") (pintype "bidirectional"))
      (node (ref "X1") (pin "L7.1") (pinfunction "P7.1_L7.1") (pintype "bidirectional"))
      (node (ref "X1") (pin "L7.2") (pinfunction "P7.2_L7.2") (pintype "bidirectional"))
      (node (ref "X1") (pin "L9.1") (pinfunction "P9.1_L9.1") (pintype "bidirectional"))
      (node (ref "X1") (pin "L9.2") (pinfunction "P9.2_L9.2") (pintype "bidirectional"))
      (node (ref "X2") (pin "L1.1") (pinfunction "P1.1_L1.1") (pintype "bidirectional"))
      (node (ref "X2") (pin "L1.2") (pinfunction "P1.2_L1.2") (pintype "bidirectional"))
    )
    (net (code "4") (name "GPA0") (class "Default")
      (node (ref "IC2") (pin "21") (pinfunction "GPA0_21") (pintype "bidirectional"))
      (node (ref "R34") (pin "1") (pinfunction "1_1") (pintype "passive"))
      (node (ref "U1") (pin "1") (pinfunction "A_1") (pintype "input"))
    )
    (net (code "5") (name "GPA1") (class "Default")
      (node (ref "IC2") (pin "22") (pinfunction "GPA1_22") (pintype "bidirectional"))
      (node (ref "R33") (pin "1") (pinfunction "1_1") (pintype "passive"))
      (node (ref "U3") (pin "1") (pinfunction "A_1") (pintype "input"))
    )
    (net (code "6") (name "GPA2") (class "Default")
      (node (ref "IC2") (pin "23") (pinfunction "GPA2_23") (pintype "bidirectional"))
      (node (ref "R35") (pin "1") (pinfunction "1_1") (pintype "passive"))
      (node (ref "U5") (pin "1") (pinfunction "A_1") (pintype "input"))
    )
    (net (code "7") (name "GPA3") (class "Default")
      (node (ref "IC2") (pin "24") (pinfunction "GPA3_24") (pintype "bidirectional"))
      (node (ref "R36") (pin "1") (pinfunction "1_1") (pintype "passive"))
      (node (ref "U7") (pin "1") (pinfunction "A_1") (pintype "input"))
    )
    (net (code "8") (name "GPA4") (class "Default")
      (node (ref "IC2") (pin "25") (pinfunction "GPA4_25") (pintype "bidirectional"))
      (node (ref "R37") (pin "1") (pinfunction "1_1") (pintype "passive"))
      (node (ref "U9") (pin "1") (pinfunction "A_1") (pintype "input"))
    )
    (net (code "9") (name "GPA5") (class "Default")
      (node (ref "IC2") (pin "26") (pinfunction "GPA5_26") (pintype "bidirectional"))
      (node (ref "R38") (pin "1") (pinfunction "1_1") (pintype "passive"))
      (node (ref "U11") (pin "1") (pinfunction "A_1") (pintype "input"))
    )
    (net (code "10") (name "GPA6") (class "Default")
      (node (ref "IC2") (pin "27") (pinfunction "GPA6_27") (pintype "bidirectional"))
      (node (ref "R39") (pin "1") (pinfunction "1_1") (pintype "passive"))
      (node (ref "U13") (pin "1") (pinfunction "A_1") (pintype "input"))
    )
    (net (code "11") (name "GPA7") (class "Default")
      (node (ref "IC2") (pin "28") (pinfunction "GPA7_28") (pintype "bidirectional"))
      (node (ref "R40") (pin "1") (pinfunction "1_1") (pintype "passive"))
      (node (ref "U15") (pin "1") (pinfunction "A_1") (pintype "input"))
    )
    (net (code "12") (name "Net-(IC2-A0)") (class "Default")
      (node (ref "IC2") (pin "15") (pinfunction "A0_15") (pintype "input"))
      (node (ref "JP3") (pin "4") (pinfunction "4_4") (pintype "passive"))
    )
    (net (code "13") (name "Net-(IC2-A1)") (class "Default")
      (node (ref "IC2") (pin "16") (pinfunction "A1_16") (pintype "input"))
      (node (ref "JP3") (pin "3") (pinfunction "3_3") (pintype "passive"))
    )
    (net (code "14") (name "Net-(IC2-GPB0)") (class "Default")
      (node (ref "IC2") (pin "1") (pinfunction "GPB0_1") (pintype "bidirectional"))
      (node (ref "X1") (pin "L2.1") (pinfunction "P2.1_L2.1") (pintype "bidirectional"))
      (node (ref "X1") (pin "L2.2") (pinfunction "P2.2_L2.2") (pintype "bidirectional"))
    )
    (net (code "15") (name "Net-(IC2-GPB1)") (class "Default")
      (node (ref "IC2") (pin "2") (pinfunction "GPB1_2") (pintype "bidirectional"))
      (node (ref "X1") (pin "L4.1") (pinfunction "P4.1_L4.1") (pintype "bidirectional"))
      (node (ref "X1") (pin "L4.2") (pinfunction "P4.2_L4.2") (pintype "bidirectional"))
    )
    (net (code "16") (name "Net-(IC2-GPB2)") (class "Default")
      (node (ref "IC2") (pin "3") (pinfunction "GPB2_3") (pintype "bidirectional"))
      (node (ref "X1") (pin "L6.1") (pinfunction "P6.1_L6.1") (pintype "bidirectional"))
      (node (ref "X1") (pin "L6.2") (pinfunction "P6.2_L6.2") (pintype "bidirectional"))
    )
    (net (code "17") (name "Net-(IC2-GPB3)") (class "Default")
      (node (ref "IC2") (pin "4") (pinfunction "GPB3_4") (pintype "bidirectional"))
      (node (ref "X1") (pin "L8.1") (pinfunction "P8.1_L8.1") (pintype "bidirectional"))
      (node (ref "X1") (pin "L8.2") (pinfunction "P8.2_L8.2") (pintype "bidirectional"))
    )
    (net (code "18") (name "Net-(IC2-GPB4)") (class "Default")
      (node (ref "IC2") (pin "5") (pinfunction "GPB4_5") (pintype "bidirectional"))
      (node (ref "X1") (pin "L10.1") (pinfunction "P10.1_L10.1") (pintype "bidirectional"))
      (node (ref "X1") (pin "L10.2") (pinfunction "P10.2_L10.2") (pintype "bidirectional"))
    )
    (net (code "19") (name "Net-(IC2-GPB5)") (class "Default")
      (node (ref "IC2") (pin "6") (pinfunction "GPB5_6") (pintype "bidirectional"))
      (node (ref "X1") (pin "L12.1") (pinfunction "P12.1_L12.1") (pintype "bidirectional"))
      (node (ref "X1") (pin "L12.2") (pinfunction "P12.2_L12.2") (pintype "bidirectional"))
    )
    (net (code "20") (name "Net-(IC2-INTB)") (class "Default")
      (node (ref "IC2") (pin "19") (pinfunction "INTB_19") (pintype "output"))
      (node (ref "JP4") (pin "1") (pinfunction "1_1") (pintype "passive"))
    )
    (net (code "21") (name "Net-(IC2-SCL)") (class "Default")
      (node (ref "IC2") (pin "12") (pinfunction "SCL_12") (pintype "input"))
      (node (ref "JP1") (pin "2") (pinfunction "2_2") (pintype "passive"))
      (node (ref "JP5") (pin "2") (pinfunction "2_2") (pintype "passive"))
    )
    (net (code "22") (name "Net-(IC2-SDA)") (class "Default")
      (node (ref "IC2") (pin "13") (pinfunction "SDA_13") (pintype "bidirectional"))
      (node (ref "JP1") (pin "1") (pinfunction "1_1") (pintype "passive"))
      (node (ref "JP5") (pin "1") (pinfunction "1_1") (pintype "passive"))
    )
    (net (code "23") (name "Net-(IC2-~{RESET})") (class "Default")
      (node (ref "C20") (pin "1") (pinfunction "1_1") (pintype "passive"))
      (node (ref "IC2") (pin "18") (pinfunction "~{RESET}_18") (pintype "input"))
      (node (ref "JP4") (pin "2") (pinfunction "2_2") (pintype "passive"))
    )
    (net (code "24") (name "Net-(LED1-C)") (class "Default")
      (node (ref "D1") (pin "A") (pinfunction "A_A") (pintype "passive"))
      (node (ref "K1") (pin "A2") (pinfunction "A2_A2") (pintype "passive"))
      (node (ref "LED1") (pin "K") (pinfunction "C_K") (pintype "passive"))
      (node (ref "U2") (pin "3") (pinfunction "D_3") (pintype "passive"))
    )
    (net (code "25") (name "Net-(LED1-PadA)") (class "Default")
      (node (ref "LED1") (pin "A") (pinfunction "A_A") (pintype "passive"))
      (node (ref "R4") (pin "1") (pinfunction "1_1") (pintype "passive"))
    )
    (net (code "26") (name "Net-(LED2-C)") (class "Default")
      (node (ref "D2") (pin "A") (pinfunction "A_A") (pintype "passive"))
      (node (ref "K2") (pin "A2") (pinfunction "A2_A2") (pintype "passive"))
      (node (ref "LED2") (pin "K") (pinfunction "C_K") (pintype "passive"))
      (node (ref "U4") (pin "3") (pinfunction "D_3") (pintype "passive"))
    )
    (net (code "27") (name "Net-(LED2-PadA)") (class "Default")
      (node (ref "LED2") (pin "A") (pinfunction "A_A") (pintype "passive"))
      (node (ref "R8") (pin "1") (pinfunction "1_1") (pintype "passive"))
    )
    (net (code "28") (name "Net-(LED3-C)") (class "Default")
      (node (ref "D3") (pin "A") (pinfunction "A_A") (pintype "passive"))
      (node (ref "K3") (pin "A2") (pinfunction "A2_A2") (pintype "passive"))
      (node (ref "LED3") (pin "K") (pinfunction "C_K") (pintype "passive"))
      (node (ref "U6") (pin "3") (pinfunction "D_3") (pintype "passive"))
    )
    (net (code "29") (name "Net-(LED3-PadA)") (class "Default")
      (node (ref "LED3") (pin "A") (pinfunction "A_A") (pintype "passive"))
      (node (ref "R12") (pin "1") (pinfunction "1_1") (pintype "passive"))
    )
    (net (code "30") (name "Net-(LED4-C)") (class "Default")
      (node (ref "D4") (pin "A") (pinfunction "A_A") (pintype "passive"))
      (node (ref "K4") (pin "A2") (pinfunction "A2_A2") (pintype "passive"))
      (node (ref "LED4") (pin "K") (pinfunction "C_K") (pintype "passive"))
      (node (ref "U8") (pin "3") (pinfunction "D_3") (pintype "passive"))
    )
    (net (code "31") (name "Net-(LED4-PadA)") (class "Default")
      (node (ref "LED4") (pin "A") (pinfunction "A_A") (pintype "passive"))
      (node (ref "R16") (pin "1") (pinfunction "1_1") (pintype "passive"))
    )
    (net (code "32") (name "Net-(LED5-C)") (class "Default")
      (node (ref "D5") (pin "A") (pinfunction "A_A") (pintype "passive"))
      (node (ref "K5") (pin "A2") (pinfunction "A2_A2") (pintype "passive"))
      (node (ref "LED5") (pin "K") (pinfunction "C_K") (pintype "passive"))
      (node (ref "U10") (pin "3") (pinfunction "D_3") (pintype "passive"))
    )
    (net (code "33") (name "Net-(LED5-PadA)") (class "Default")
      (node (ref "LED5") (pin "A") (pinfunction "A_A") (pintype "passive"))
      (node (ref "R20") (pin "1") (pinfunction "1_1") (pintype "passive"))
    )
    (net (code "34") (name "Net-(LED6-C)") (class "Default")
      (node (ref "D6") (pin "A") (pinfunction "A_A") (pintype "passive"))
      (node (ref "K6") (pin "A2") (pinfunction "A2_A2") (pintype "passive"))
      (node (ref "LED6") (pin "K") (pinfunction "C_K") (pintype "passive"))
      (node (ref "U12") (pin "3") (pinfunction "D_3") (pintype "passive"))
    )
    (net (code "35") (name "Net-(LED6-PadA)") (class "Default")
      (node (ref "LED6") (pin "A") (pinfunction "A_A") (pintype "passive"))
      (node (ref "R24") (pin "1") (pinfunction "1_1") (pintype "passive"))
    )
    (net (code "36") (name "Net-(LED7-C)") (class "Default")
      (node (ref "D7") (pin "A") (pinfunction "A_A") (pintype "passive"))
      (node (ref "K7") (pin "A2") (pinfunction "A2_A2") (pintype "passive"))
      (node (ref "LED7") (pin "K") (pinfunction "C_K") (pintype "passive"))
      (node (ref "U14") (pin "3") (pinfunction "D_3") (pintype "passive"))
    )
    (net (code "37") (name "Net-(LED7-PadA)") (class "Default")
      (node (ref "LED7") (pin "A") (pinfunction "A_A") (pintype "passive"))
      (node (ref "R28") (pin "1") (pinfunction "1_1") (pintype "passive"))
    )
    (net (code "38") (name "Net-(LED8-C)") (class "Default")
      (node (ref "D8") (pin "A") (pinfunction "A_A") (pintype "passive"))
      (node (ref "K8") (pin "A2") (pinfunction "A2_A2") (pintype "passive"))
      (node (ref "LED8") (pin "K") (pinfunction "C_K") (pintype "passive"))
      (node (ref "U16") (pin "3") (pinfunction "D_3") (pintype "passive"))
    )
    (net (code "39") (name "Net-(LED8-PadA)") (class "Default")
      (node (ref "LED8") (pin "A") (pinfunction "A_A") (pintype "passive"))
      (node (ref "R32") (pin "1") (pinfunction "1_1") (pintype "passive"))
    )
    (net (code "40") (name "Net-(R1-Pad2)") (class "Default")
      (node (ref "R1") (pin "2") (pinfunction "2_2") (pintype "passive"))
      (node (ref "R2") (pin "2") (pinfunction "2_2") (pintype "passive"))
      (node (ref "S1") (pin "2/C") (pinfunction "2/C_2/C") (pintype "passive"))
    )
    (net (code "41") (name "Net-(R5-Pad2)") (class "Default")
      (node (ref "R5") (pin "2") (pinfunction "2_2") (pintype "passive"))
      (node (ref "R6") (pin "2") (pinfunction "2_2") (pintype "passive"))
      (node (ref "S2") (pin "2/C") (pinfunction "2/C_2/C") (pintype "passive"))
    )
    (net (code "42") (name "Net-(R10-Pad2)") (class "Default")
      (node (ref "R10") (pin "2") (pinfunction "2_2") (pintype "passive"))
      (node (ref "R9") (pin "2") (pinfunction "2_2") (pintype "passive"))
      (node (ref "S3") (pin "2/C") (pinfunction "2/C_2/C") (pintype "passive"))
    )
    (net (code "43") (name "Net-(R13-Pad2)") (class "Default")
      (node (ref "R13") (pin "2") (pinfunction "2_2") (pintype "passive"))
      (node (ref "R14") (pin "2") (pinfunction "2_2") (pintype "passive"))
      (node (ref "S4") (pin "2/C") (pinfunction "2/C_2/C") (pintype "passive"))
    )
    (net (code "44") (name "Net-(R17-Pad2)") (class "Default")
      (node (ref "R17") (pin "2") (pinfunction "2_2") (pintype "passive"))
      (node (ref "R18") (pin "2") (pinfunction "2_2") (pintype "passive"))
      (node (ref "S5") (pin "2/C") (pinfunction "2/C_2/C") (pintype "passive"))
    )
    (net (code "45") (name "Net-(R21-Pad2)") (class "Default")
      (node (ref "R21") (pin "2") (pinfunction "2_2") (pintype "passive"))
      (node (ref "R22") (pin "2") (pinfunction "2_2") (pintype "passive"))
      (node (ref "S6") (pin "2/C") (pinfunction "2/C_2/C") (pintype "passive"))
    )
    (net (code "46") (name "Net-(R25-Pad2)") (class "Default")
      (node (ref "R25") (pin "2") (pinfunction "2_2") (pintype "passive"))
      (node (ref "R26") (pin "2") (pinfunction "2_2") (pintype "passive"))
      (node (ref "S7") (pin "2/C") (pinfunction "2/C_2/C") (pintype "passive"))
    )
    (net (code "47") (name "Net-(R29-Pad2)") (class "Default")
      (node (ref "R29") (pin "2") (pinfunction "2_2") (pintype "passive"))
      (node (ref "R30") (pin "2") (pinfunction "2_2") (pintype "passive"))
      (node (ref "S8") (pin "2/C") (pinfunction "2/C_2/C") (pintype "passive"))
    )
    (net (code "48") (name "Net-(U1-B)") (class "Default")
      (node (ref "C4") (pin "+") (pinfunction "+_+") (pintype "passive"))
      (node (ref "R2") (pin "1") (pinfunction "1_1") (pintype "passive"))
      (node (ref "U1") (pin "2") (pinfunction "B_2") (pintype "input"))
    )
    (net (code "49") (name "Net-(U1-Y)") (class "Default")
      (node (ref "R3") (pin "2") (pinfunction "2_2") (pintype "passive"))
      (node (ref "U1") (pin "4") (pinfunction "Y_4") (pintype "output"))
      (node (ref "U2") (pin "1") (pinfunction "G_1") (pintype "passive"))
    )
    (net (code "50") (name "Net-(U3-B)") (class "Default")
      (node (ref "C6") (pin "+") (pinfunction "+_+") (pintype "passive"))
      (node (ref "R6") (pin "1") (pinfunction "1_1") (pintype "passive"))
      (node (ref "U3") (pin "2") (pinfunction "B_2") (pintype "input"))
    )
    (net (code "51") (name "Net-(U3-Y)") (class "Default")
      (node (ref "R7") (pin "2") (pinfunction "2_2") (pintype "passive"))
      (node (ref "U3") (pin "4") (pinfunction "Y_4") (pintype "output"))
      (node (ref "U4") (pin "1") (pinfunction "G_1") (pintype "passive"))
    )
    (net (code "52") (name "Net-(U5-B)") (class "Default")
      (node (ref "C8") (pin "+") (pinfunction "+_+") (pintype "passive"))
      (node (ref "R10") (pin "1") (pinfunction "1_1") (pintype "passive"))
      (node (ref "U5") (pin "2") (pinfunction "B_2") (pintype "input"))
    )
    (net (code "53") (name "Net-(U5-Y)") (class "Default")
      (node (ref "R11") (pin "2") (pinfunction "2_2") (pintype "passive"))
      (node (ref "U5") (pin "4") (pinfunction "Y_4") (pintype "output"))
      (node (ref "U6") (pin "1") (pinfunction "G_1") (pintype "passive"))
    )
    (net (code "54") (name "Net-(U7-B)") (class "Default")
      (node (ref "C10") (pin "+") (pinfunction "+_+") (pintype "passive"))
      (node (ref "R14") (pin "1") (pinfunction "1_1") (pintype "passive"))
      (node (ref "U7") (pin "2") (pinfunction "B_2") (pintype "input"))
    )
    (net (code "55") (name "Net-(U7-Y)") (class "Default")
      (node (ref "R15") (pin "2") (pinfunction "2_2") (pintype "passive"))
      (node (ref "U7") (pin "4") (pinfunction "Y_4") (pintype "output"))
      (node (ref "U8") (pin "1") (pinfunction "G_1") (pintype "passive"))
    )
    (net (code "56") (name "Net-(U9-B)") (class "Default")
      (node (ref "C12") (pin "+") (pinfunction "+_+") (pintype "passive"))
      (node (ref "R18") (pin "1") (pinfunction "1_1") (pintype "passive"))
      (node (ref "U9") (pin "2") (pinfunction "B_2") (pintype "input"))
    )
    (net (code "57") (name "Net-(U10-G)") (class "Default")
      (node (ref "R19") (pin "2") (pinfunction "2_2") (pintype "passive"))
      (node (ref "U10") (pin "1") (pinfunction "G_1") (pintype "passive"))
      (node (ref "U9") (pin "4") (pinfunction "Y_4") (pintype "output"))
    )
    (net (code "58") (name "Net-(U11-B)") (class "Default")
      (node (ref "C14") (pin "+") (pinfunction "+_+") (pintype "passive"))
      (node (ref "R22") (pin "1") (pinfunction "1_1") (pintype "passive"))
      (node (ref "U11") (pin "2") (pinfunction "B_2") (pintype "input"))
    )
    (net (code "59") (name "Net-(U11-Y)") (class "Default")
      (node (ref "R23") (pin "2") (pinfunction "2_2") (pintype "passive"))
      (node (ref "U11") (pin "4") (pinfunction "Y_4") (pintype "output"))
      (node (ref "U12") (pin "1") (pinfunction "G_1") (pintype "passive"))
    )
    (net (code "60") (name "Net-(U13-B)") (class "Default")
      (node (ref "C16") (pin "+") (pinfunction "+_+") (pintype "passive"))
      (node (ref "R26") (pin "1") (pinfunction "1_1") (pintype "passive"))
      (node (ref "U13") (pin "2") (pinfunction "B_2") (pintype "input"))
    )
    (net (code "61") (name "Net-(U13-Y)") (class "Default")
      (node (ref "R27") (pin "2") (pinfunction "2_2") (pintype "passive"))
      (node (ref "U13") (pin "4") (pinfunction "Y_4") (pintype "output"))
      (node (ref "U14") (pin "1") (pinfunction "G_1") (pintype "passive"))
    )
    (net (code "62") (name "Net-(U15-B)") (class "Default")
      (node (ref "C18") (pin "+") (pinfunction "+_+") (pintype "passive"))
      (node (ref "R30") (pin "1") (pinfunction "1_1") (pintype "passive"))
      (node (ref "U15") (pin "2") (pinfunction "B_2") (pintype "input"))
    )
    (net (code "63") (name "Net-(U15-Y)") (class "Default")
      (node (ref "R31") (pin "2") (pinfunction "2_2") (pintype "passive"))
      (node (ref "U15") (pin "4") (pinfunction "Y_4") (pintype "output"))
      (node (ref "U16") (pin "1") (pinfunction "G_1") (pintype "passive"))
    )
    (net (code "64") (name "Net-(X3-P1.1)") (class "Default")
      (node (ref "K1") (pin "S") (pinfunction "S_S") (pintype "passive"))
      (node (ref "X3") (pin "L1.1") (pinfunction "P1.1_L1.1") (pintype "bidirectional"))
      (node (ref "X3") (pin "L1.2") (pinfunction "P1.2_L1.2") (pintype "bidirectional"))
    )
    (net (code "65") (name "Net-(X3-P2.1)") (class "Default")
      (node (ref "K1") (pin "P") (pinfunction "P_P") (pintype "passive"))
      (node (ref "X3") (pin "L2.1") (pinfunction "P2.1_L2.1") (pintype "bidirectional"))
      (node (ref "X3") (pin "L2.2") (pinfunction "P2.2_L2.2") (pintype "bidirectional"))
    )
    (net (code "66") (name "Net-(X4-P1.1)") (class "Default")
      (node (ref "K2") (pin "S") (pinfunction "S_S") (pintype "passive"))
      (node (ref "X4") (pin "L1.1") (pinfunction "P1.1_L1.1") (pintype "bidirectional"))
      (node (ref "X4") (pin "L1.2") (pinfunction "P1.2_L1.2") (pintype "bidirectional"))
    )
    (net (code "67") (name "Net-(X4-P2.1)") (class "Default")
      (node (ref "K2") (pin "P") (pinfunction "P_P") (pintype "passive"))
      (node (ref "X4") (pin "L2.1") (pinfunction "P2.1_L2.1") (pintype "bidirectional"))
      (node (ref "X4") (pin "L2.2") (pinfunction "P2.2_L2.2") (pintype "bidirectional"))
    )
    (net (code "68") (name "Net-(X5-P1.1)") (class "Default")
      (node (ref "K3") (pin "S") (pinfunction "S_S") (pintype "passive"))
      (node (ref "X5") (pin "L1.1") (pinfunction "P1.1_L1.1") (pintype "bidirectional"))
      (node (ref "X5") (pin "L1.2") (pinfunction "P1.2_L1.2") (pintype "bidirectional"))
    )
    (net (code "69") (name "Net-(X5-P2.1)") (class "Default")
      (node (ref "K3") (pin "P") (pinfunction "P_P") (pintype "passive"))
      (node (ref "X5") (pin "L2.1") (pinfunction "P2.1_L2.1") (pintype "bidirectional"))
      (node (ref "X5") (pin "L2.2") (pinfunction "P2.2_L2.2") (pintype "bidirectional"))
    )
    (net (code "70") (name "Net-(X6-P1.1)") (class "Default")
      (node (ref "K4") (pin "S") (pinfunction "S_S") (pintype "passive"))
      (node (ref "X6") (pin "L1.1") (pinfunction "P1.1_L1.1") (pintype "bidirectional"))
      (node (ref "X6") (pin "L1.2") (pinfunction "P1.2_L1.2") (pintype "bidirectional"))
    )
    (net (code "71") (name "Net-(X6-P2.1)") (class "Default")
      (node (ref "K4") (pin "P") (pinfunction "P_P") (pintype "passive"))
      (node (ref "X6") (pin "L2.1") (pinfunction "P2.1_L2.1") (pintype "bidirectional"))
      (node (ref "X6") (pin "L2.2") (pinfunction "P2.2_L2.2") (pintype "bidirectional"))
    )
    (net (code "72") (name "Net-(X7-P1.1)") (class "Default")
      (node (ref "K5") (pin "S") (pinfunction "S_S") (pintype "passive"))
      (node (ref "X7") (pin "L1.1") (pinfunction "P1.1_L1.1") (pintype "bidirectional"))
      (node (ref "X7") (pin "L1.2") (pinfunction "P1.2_L1.2") (pintype "bidirectional"))
    )
    (net (code "73") (name "Net-(X7-P2.1)") (class "Default")
      (node (ref "K5") (pin "P") (pinfunction "P_P") (pintype "passive"))
      (node (ref "X7") (pin "L2.1") (pinfunction "P2.1_L2.1") (pintype "bidirectional"))
      (node (ref "X7") (pin "L2.2") (pinfunction "P2.2_L2.2") (pintype "bidirectional"))
    )
    (net (code "74") (name "Net-(X8-P1.1)") (class "Default")
      (node (ref "K6") (pin "S") (pinfunction "S_S") (pintype "passive"))
      (node (ref "X8") (pin "L1.1") (pinfunction "P1.1_L1.1") (pintype "bidirectional"))
      (node (ref "X8") (pin "L1.2") (pinfunction "P1.2_L1.2") (pintype "bidirectional"))
    )
    (net (code "75") (name "Net-(X8-P2.1)") (class "Default")
      (node (ref "K6") (pin "P") (pinfunction "P_P") (pintype "passive"))
      (node (ref "X8") (pin "L2.1") (pinfunction "P2.1_L2.1") (pintype "bidirectional"))
      (node (ref "X8") (pin "L2.2") (pinfunction "P2.2_L2.2") (pintype "bidirectional"))
    )
    (net (code "76") (name "Net-(X9-P1.1)") (class "Default")
      (node (ref "K7") (pin "S") (pinfunction "S_S") (pintype "passive"))
      (node (ref "X9") (pin "L1.1") (pinfunction "P1.1_L1.1") (pintype "bidirectional"))
      (node (ref "X9") (pin "L1.2") (pinfunction "P1.2_L1.2") (pintype "bidirectional"))
    )
    (net (code "77") (name "Net-(X9-P2.1)") (class "Default")
      (node (ref "K7") (pin "P") (pinfunction "P_P") (pintype "passive"))
      (node (ref "X9") (pin "L2.1") (pinfunction "P2.1_L2.1") (pintype "bidirectional"))
      (node (ref "X9") (pin "L2.2") (pinfunction "P2.2_L2.2") (pintype "bidirectional"))
    )
    (net (code "78") (name "Net-(X10-P1.1)") (class "Default")
      (node (ref "K8") (pin "S") (pinfunction "S_S") (pintype "passive"))
      (node (ref "X10") (pin "L1.1") (pinfunction "P1.1_L1.1") (pintype "bidirectional"))
      (node (ref "X10") (pin "L1.2") (pinfunction "P1.2_L1.2") (pintype "bidirectional"))
    )
    (net (code "79") (name "Net-(X10-P2.1)") (class "Default")
      (node (ref "K8") (pin "P") (pinfunction "P_P") (pintype "passive"))
      (node (ref "X10") (pin "L2.1") (pinfunction "P2.1_L2.1") (pintype "bidirectional"))
      (node (ref "X10") (pin "L2.2") (pinfunction "P2.2_L2.2") (pintype "bidirectional"))
    )
    (net (code "80") (name "unconnected-(H3-MOUNT-PadB3,0)") (class "Default")
      (node (ref "H3") (pin "B3,0") (pinfunction "MOUNT_B3,0") (pintype "passive"))
    )
    (net (code "81") (name "unconnected-(H4-MOUNT-PadB3,0)") (class "Default")
      (node (ref "H4") (pin "B3,0") (pinfunction "MOUNT_B3,0") (pintype "passive"))
    )
    (net (code "82") (name "unconnected-(IC2-INTA-Pad20)") (class "Default")
      (node (ref "IC2") (pin "20") (pinfunction "INTA_20") (pintype "output"))
    )
    (net (code "83") (name "unconnected-(S1-Pad1)") (class "Default")
      (node (ref "S1") (pin "1") (pinfunction "1_1") (pintype "passive"))
    )
    (net (code "84") (name "unconnected-(S2-Pad1)") (class "Default")
      (node (ref "S2") (pin "1") (pinfunction "1_1") (pintype "passive"))
    )
    (net (code "85") (name "unconnected-(S3-Pad1)") (class "Default")
      (node (ref "S3") (pin "1") (pinfunction "1_1") (pintype "passive"))
    )
    (net (code "86") (name "unconnected-(S4-Pad1)") (class "Default")
      (node (ref "S4") (pin "1") (pinfunction "1_1") (pintype "passive"))
    )
    (net (code "87") (name "unconnected-(S5-Pad1)") (class "Default")
      (node (ref "S5") (pin "1") (pinfunction "1_1") (pintype "passive"))
    )
    (net (code "88") (name "unconnected-(S6-Pad1)") (class "Default")
      (node (ref "S6") (pin "1") (pinfunction "1_1") (pintype "passive"))
    )
    (net (code "89") (name "unconnected-(S7-Pad1)") (class "Default")
      (node (ref "S7") (pin "1") (pinfunction "1_1") (pintype "passive"))
    )
    (net (code "90") (name "unconnected-(S8-Pad1)") (class "Default")
      (node (ref "S8") (pin "1") (pinfunction "1_1") (pintype "passive"))
    )
  )
)
